# Inverter_540VDC_V2_2.net
KiCad netlist of a schematic drawn in Altium Designer
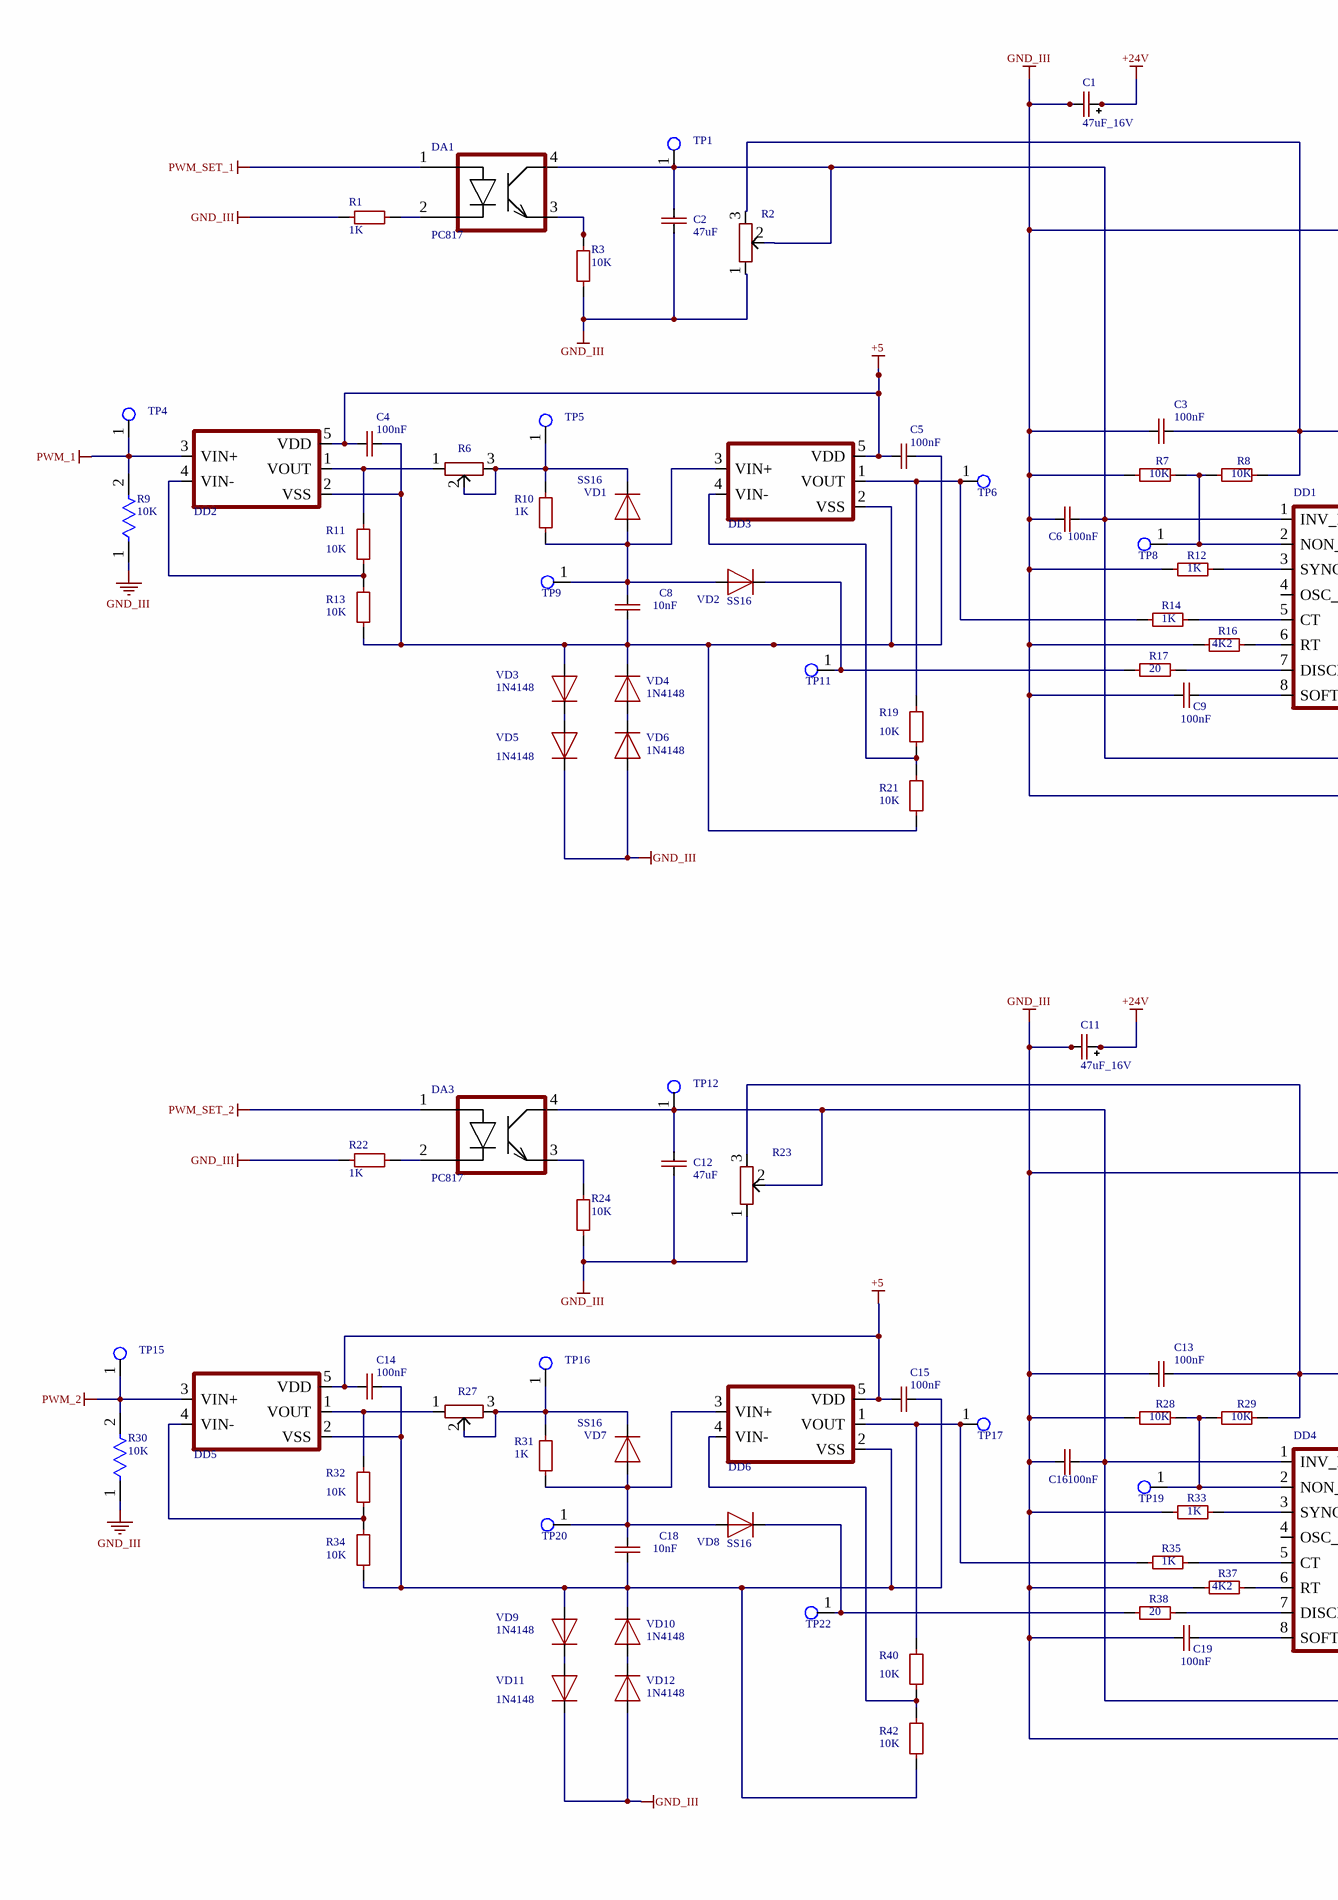
[diagram p0: Inverter_540VDC_V2.2.SchDoc, top left]
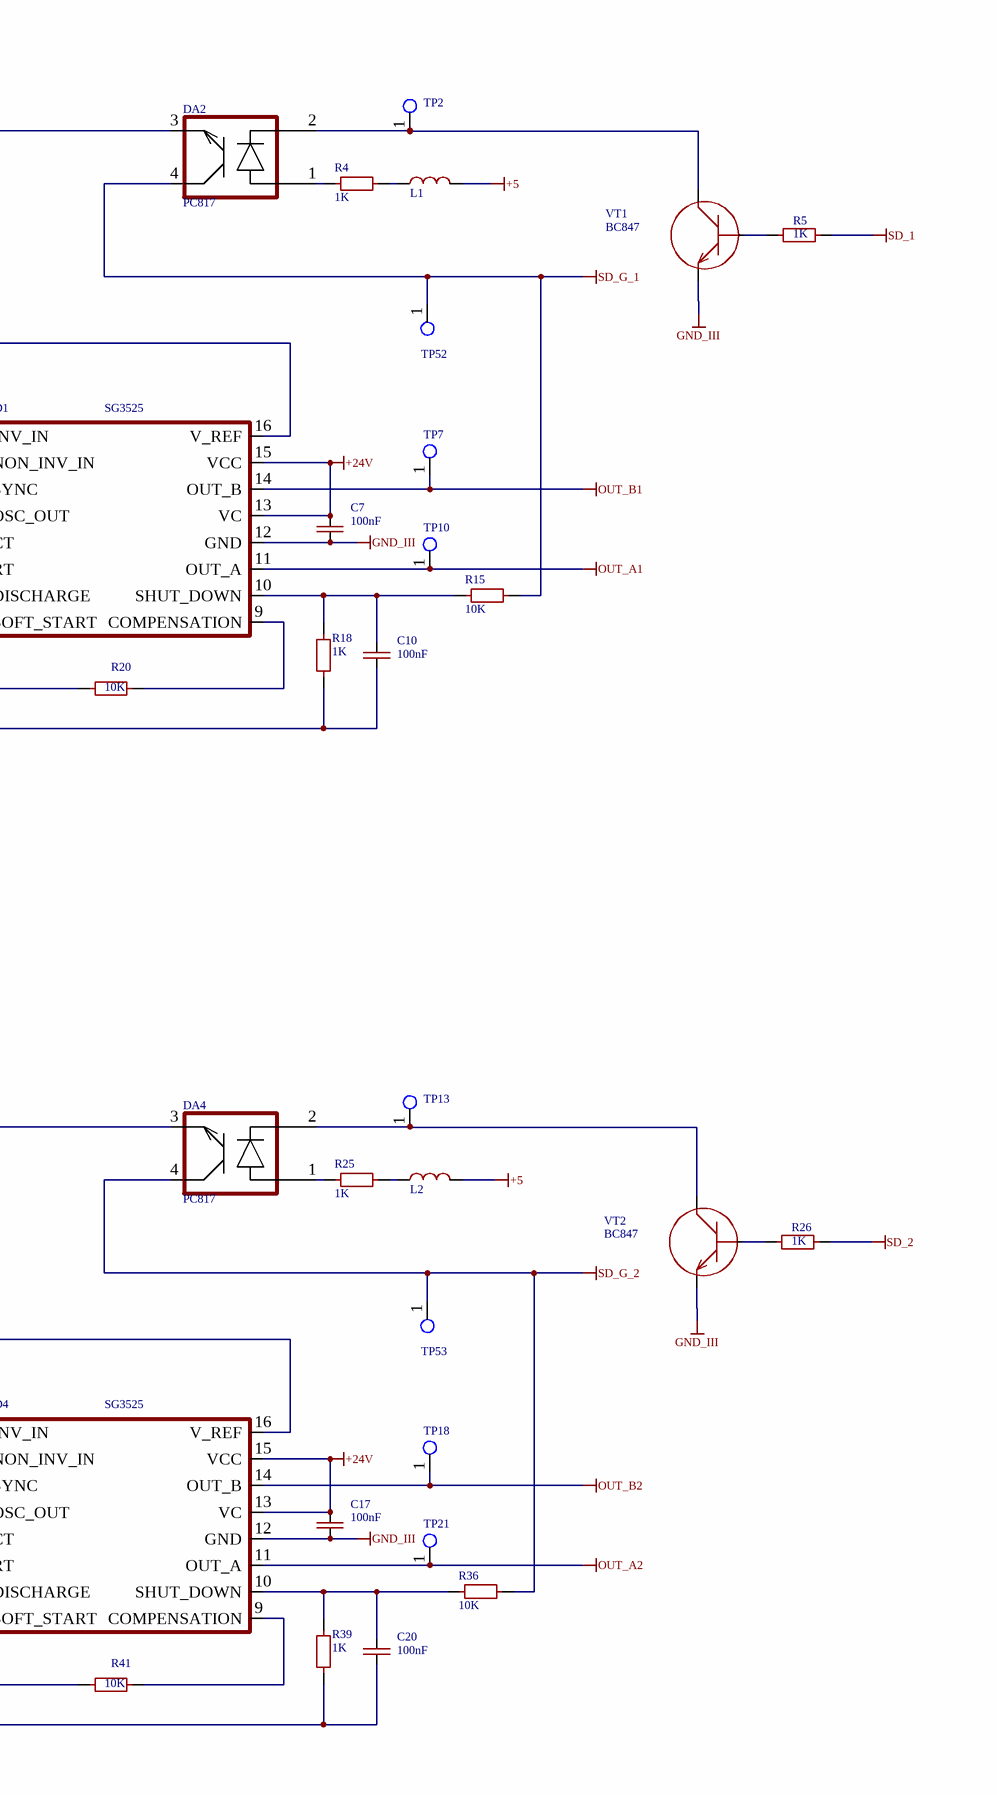
[diagram p1: Inverter_540VDC_V2.2.SchDoc, top right]
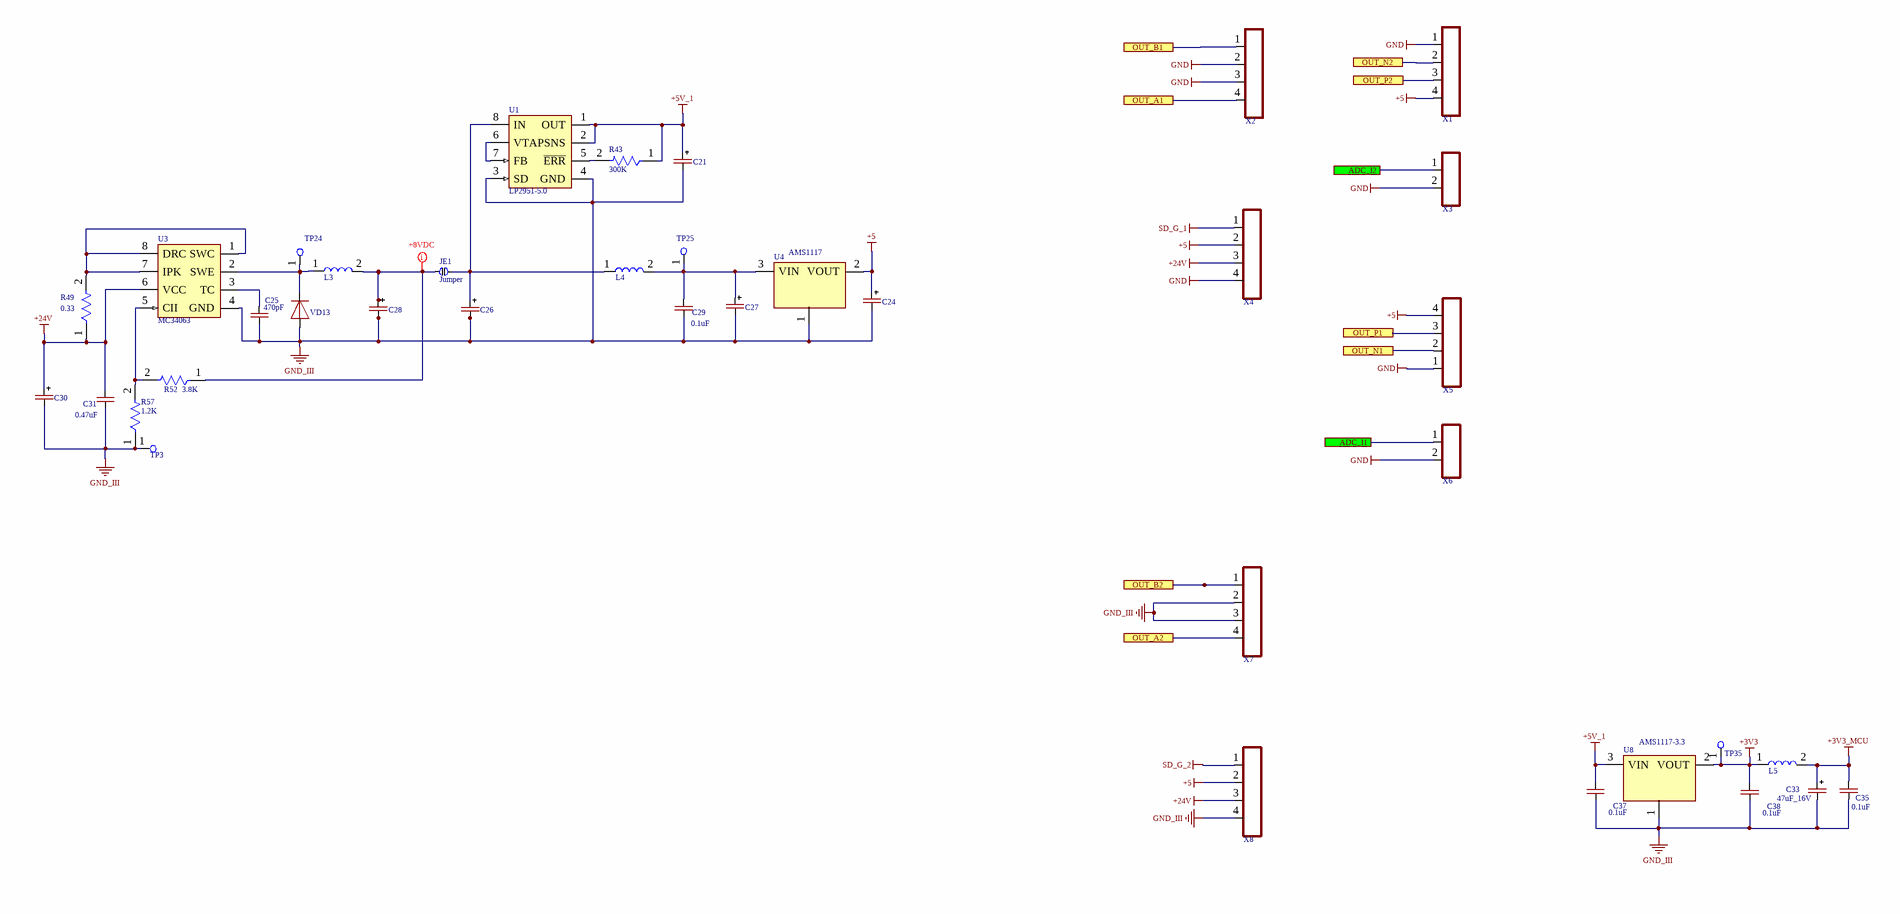
[diagram p2: Inverter_540VDC_V2.2.SchDoc, bottom left]
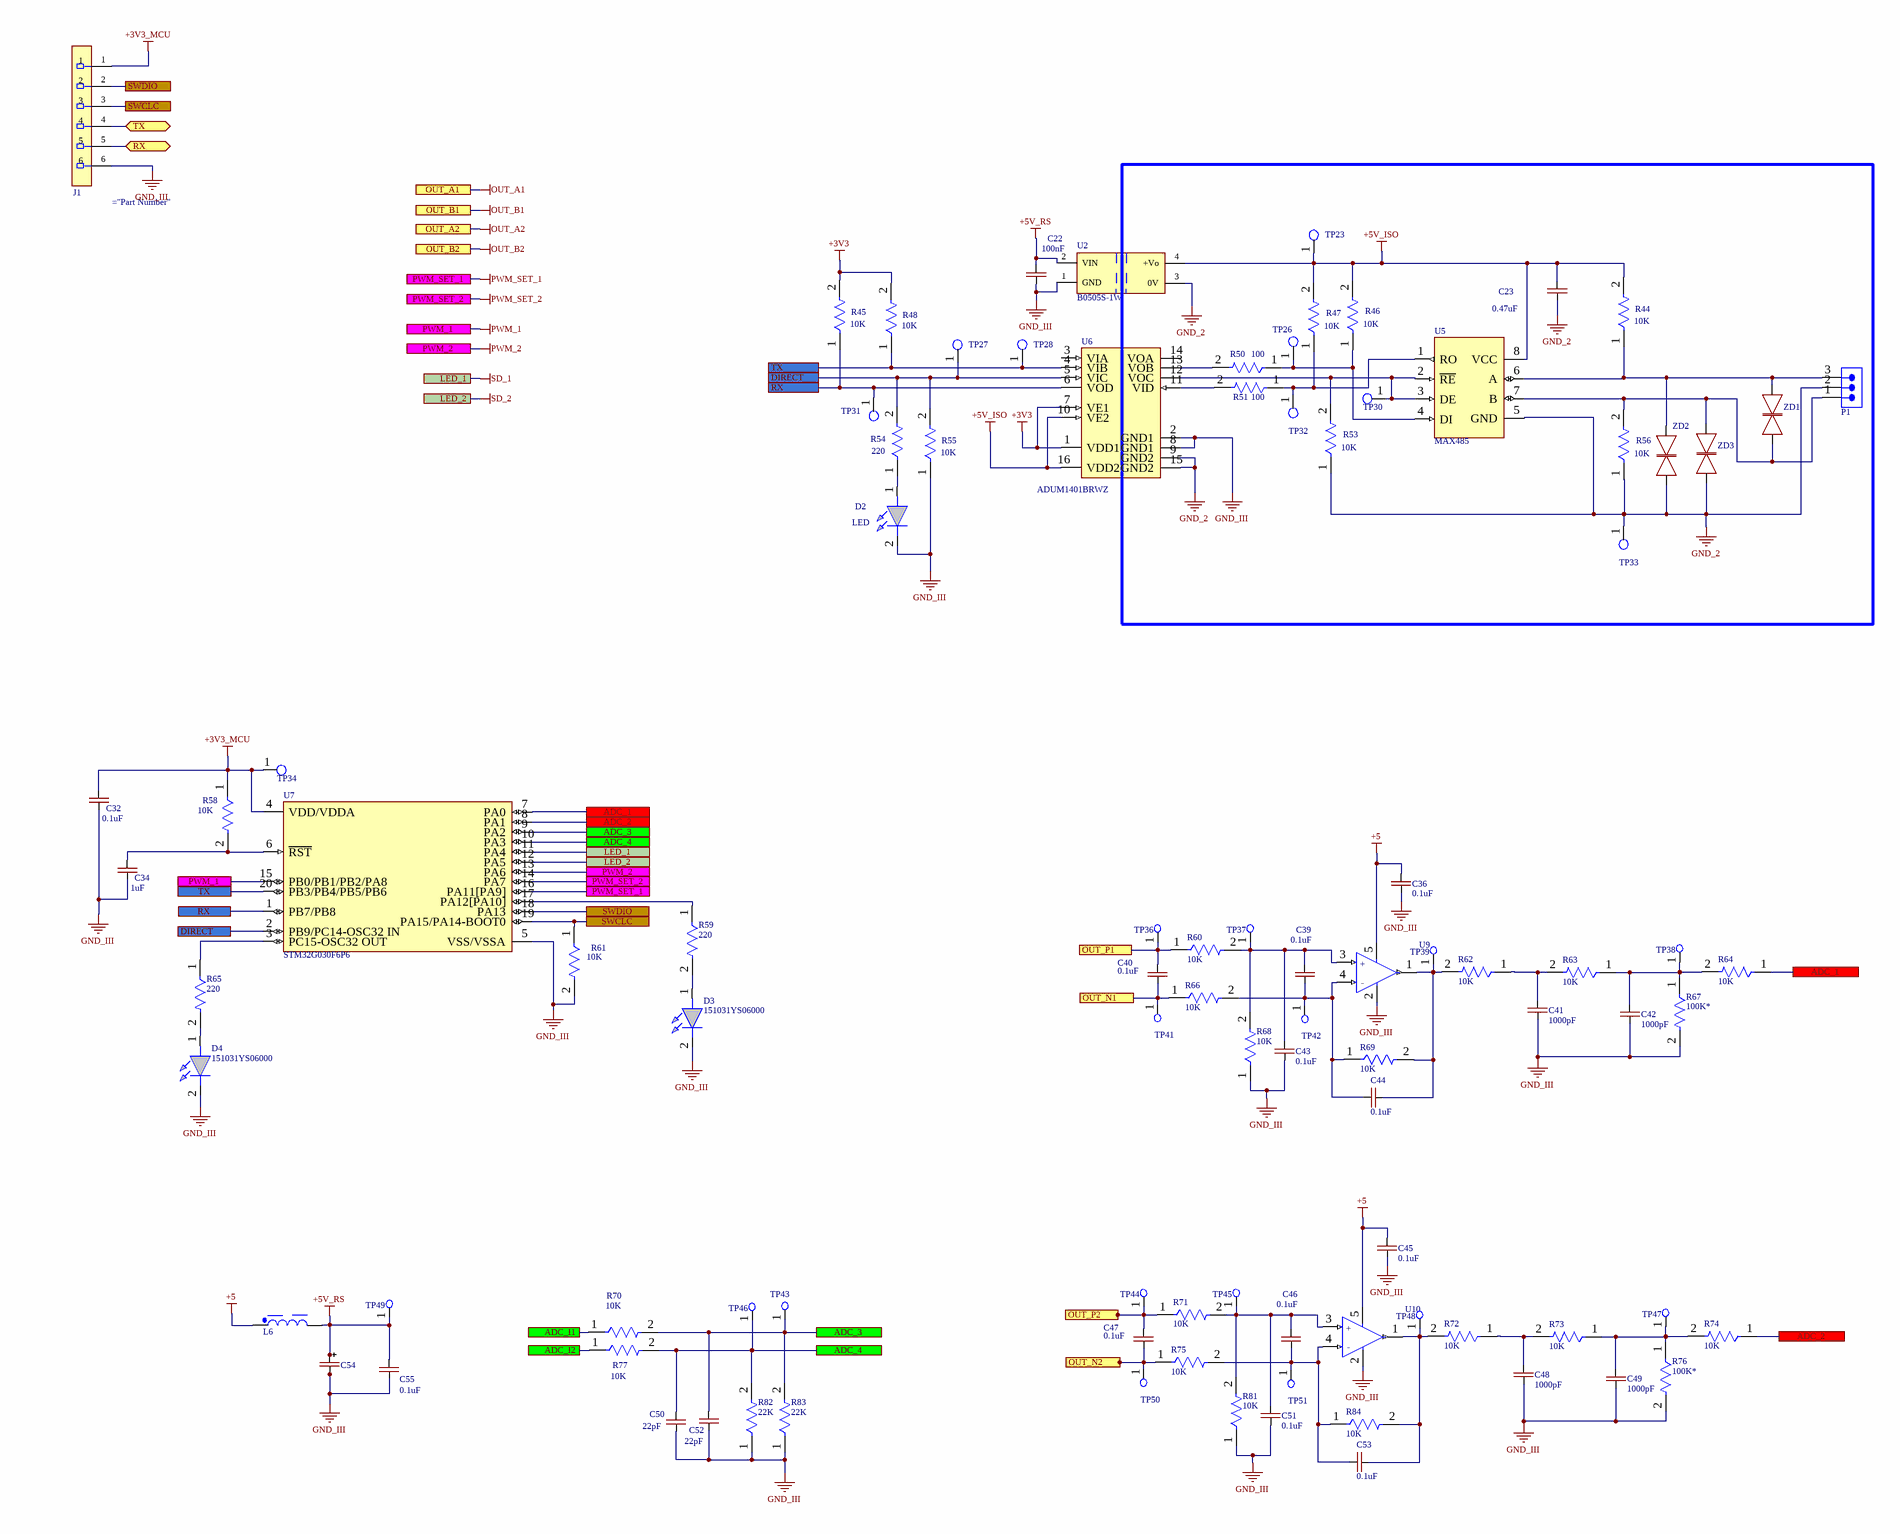
[diagram p3: Inverter_540VDC_V2.2.SchDoc, bottom right]

(export (version "E")
  (design (tool "Eeschema 10.0.6"))
  (components
    (comp (ref "C1")
      (value "47uF_16V")
      (footprint "CAP-TAN-D")
      (libsource (lib "PASSIVE_COMPONENTS") (part "CAP-POLAR"))
    )
    (comp (ref "C2")
      (value "47uF")
      (footprint "CAP-0805")
      (libsource (lib "PAS_COMPONENTS") (part "CAP-NON-POLAR"))
    )
    (comp (ref "C3")
      (value "100nF")
      (footprint "CAP-0805")
      (libsource (lib "PAS_COMPONENTS") (part "CAP-NON-POLAR"))
    )
    (comp (ref "C4")
      (value "100nF")
      (footprint "CAP-0805")
      (libsource (lib "PAS_COMPONENTS") (part "CAP-NON-POLAR"))
    )
    (comp (ref "C5")
      (value "100nF")
      (footprint "CAP-0805")
      (libsource (lib "PAS_COMPONENTS") (part "CAP-NON-POLAR"))
    )
    (comp (ref "C6")
      (value "100nF")
      (footprint "CAP-0805")
      (libsource (lib "PAS_COMPONENTS") (part "CAP-NON-POLAR"))
    )
    (comp (ref "C7")
      (value "100nF")
      (footprint "CAP-0805")
      (libsource (lib "PAS_COMPONENTS") (part "CAP-NON-POLAR"))
    )
    (comp (ref "C8")
      (value "10nF")
      (footprint "CAP-0805")
      (libsource (lib "PAS_COMPONENTS") (part "CAP-NON-POLAR"))
    )
    (comp (ref "C9")
      (value "100nF")
      (footprint "CAP-0805")
      (libsource (lib "PAS_COMPONENTS") (part "CAP-NON-POLAR"))
    )
    (comp (ref "C10")
      (value "100nF")
      (footprint "CAP-0805")
      (libsource (lib "PAS_COMPONENTS") (part "CAP-NON-POLAR"))
    )
    (comp (ref "C11")
      (value "47uF_16V")
      (footprint "CAP-TAN-D")
      (libsource (lib "PASSIVE_COMPONENTS") (part "CAP-POLAR"))
    )
    (comp (ref "C12")
      (value "47uF")
      (footprint "CAP-0805")
      (libsource (lib "PAS_COMPONENTS") (part "CAP-NON-POLAR"))
    )
    (comp (ref "C13")
      (value "100nF")
      (footprint "CAP-0805")
      (libsource (lib "PAS_COMPONENTS") (part "CAP-NON-POLAR"))
    )
    (comp (ref "C14")
      (value "100nF")
      (footprint "CAP-0805")
      (libsource (lib "PAS_COMPONENTS") (part "CAP-NON-POLAR"))
    )
    (comp (ref "C15")
      (value "100nF")
      (footprint "CAP-0805")
      (libsource (lib "PAS_COMPONENTS") (part "CAP-NON-POLAR"))
    )
    (comp (ref "C16")
      (value "100nF")
      (footprint "CAP-0805")
      (libsource (lib "PAS_COMPONENTS") (part "CAP-NON-POLAR"))
    )
    (comp (ref "C17")
      (value "100nF")
      (footprint "CAP-0805")
      (libsource (lib "PAS_COMPONENTS") (part "CAP-NON-POLAR"))
    )
    (comp (ref "C18")
      (value "10nF")
      (footprint "CAP-0805")
      (libsource (lib "PAS_COMPONENTS") (part "CAP-NON-POLAR"))
    )
    (comp (ref "C19")
      (value "100nF")
      (footprint "CAP-0805")
      (libsource (lib "PAS_COMPONENTS") (part "CAP-NON-POLAR"))
    )
    (comp (ref "C20")
      (value "100nF")
      (footprint "CAP-0805")
      (libsource (lib "PAS_COMPONENTS") (part "CAP-NON-POLAR"))
    )
    (comp (ref "C21")
      (value "CAP-POLAR")
      (footprint "CAP-TAN-C")
      (libsource (lib "PAS_COMPONENTS") (part "CAP-POLAR"))
    )
    (comp (ref "C22")
      (value "100nF")
      (footprint "CAP-0805")
      (libsource (lib "PASSIVE_COMPONENTS") (part "CAP-NON-POLAR"))
    )
    (comp (ref "C23")
      (value "0.47uF")
      (footprint "CAP-0805")
      (libsource (lib "PASSIVE_COMPONENTS") (part "CAP-NON-POLAR"))
    )
    (comp (ref "C24")
      (value "CAP-POLAR")
      (footprint "CAP-TAN-C")
      (libsource (lib "PAS_COMPONENTS") (part "CAP-POLAR"))
    )
    (comp (ref "C25")
      (value "470pF")
      (footprint "CAP-0805")
      (libsource (lib "PASSIVE_COMPONENTS") (part "CAP-NON-POLAR"))
    )
    (comp (ref "C26")
      (value "CAP-POLAR")
      (footprint "CAP-TAN-C")
      (libsource (lib "PAS_COMPONENTS") (part "CAP-POLAR"))
    )
    (comp (ref "C27")
      (value "CAP-POLAR")
      (footprint "CAP-TAN-C")
      (libsource (lib "PAS_COMPONENTS") (part "CAP-POLAR"))
    )
    (comp (ref "C28")
      (value "CAP-POLAR")
      (footprint "CAP-TAN-C")
      (libsource (lib "PAS_COMPONENTS") (part "CAP-POLAR"))
    )
    (comp (ref "C29")
      (value "0.1uF")
      (footprint "CAP-0805")
      (libsource (lib "PASSIVE_COMPONENTS") (part "CAP-NON-POLAR"))
    )
    (comp (ref "C30")
      (value "CAP-POLAR")
      (footprint "CAP-TAN-C")
      (libsource (lib "PAS_COMPONENTS") (part "CAP-POLAR"))
    )
    (comp (ref "C31")
      (value "0.47uF")
      (footprint "CAP-0805")
      (libsource (lib "PASSIVE_COMPONENTS") (part "CAP-NON-POLAR"))
    )
    (comp (ref "C32")
      (value "0.1uF")
      (footprint "CAP-0805")
      (libsource (lib "PASSIVE_COMPONENTS") (part "CAP-NON-POLAR"))
    )
    (comp (ref "C33")
      (value "47uF_16V")
      (footprint "CAP-TAN-D")
      (libsource (lib "PASSIVE_COMPONENTS") (part "CAP-POLAR"))
    )
    (comp (ref "C34")
      (value "1uF")
      (footprint "CAP-0805")
      (libsource (lib "PASSIVE_COMPONENTS") (part "CAP-NON-POLAR"))
    )
    (comp (ref "C35")
      (value "0.1uF")
      (footprint "CAP-0805")
      (libsource (lib "PASSIVE_COMPONENTS") (part "CAP-NON-POLAR"))
    )
    (comp (ref "C36")
      (value "0.1uF")
      (footprint "CAP-0805")
      (libsource (lib "PASSIVE_COMPONENTS") (part "CAP-NON-POLAR"))
    )
    (comp (ref "C37")
      (value "0.1uF")
      (footprint "CAP-0805")
      (libsource (lib "PASSIVE_COMPONENTS") (part "CAP-NON-POLAR"))
    )
    (comp (ref "C38")
      (value "0.1uF")
      (footprint "CAP-0805")
      (libsource (lib "PASSIVE_COMPONENTS") (part "CAP-NON-POLAR"))
    )
    (comp (ref "C39")
      (value "0.1uF")
      (footprint "CAP-0805")
      (libsource (lib "PASSIVE_COMPONENTS") (part "CAP-NON-POLAR"))
    )
    (comp (ref "C40")
      (value "0.1uF")
      (footprint "CAP-0805")
      (libsource (lib "PASSIVE_COMPONENTS") (part "CAP-NON-POLAR"))
    )
    (comp (ref "C41")
      (value "1000pF")
      (footprint "CAP-0805")
      (libsource (lib "PASSIVE_COMPONENTS") (part "CAP-NON-POLAR"))
    )
    (comp (ref "C42")
      (value "1000pF")
      (footprint "CAP-0805")
      (libsource (lib "PASSIVE_COMPONENTS") (part "CAP-NON-POLAR"))
    )
    (comp (ref "C43")
      (value "0.1uF")
      (footprint "CAP-0805")
      (libsource (lib "PASSIVE_COMPONENTS") (part "CAP-NON-POLAR"))
    )
    (comp (ref "C44")
      (value "0.1uF")
      (footprint "CAP-0805")
      (libsource (lib "PASSIVE_COMPONENTS") (part "CAP-NON-POLAR"))
    )
    (comp (ref "C45")
      (value "0.1uF")
      (footprint "CAP-0805")
      (libsource (lib "PASSIVE_COMPONENTS") (part "CAP-NON-POLAR"))
    )
    (comp (ref "C46")
      (value "0.1uF")
      (footprint "CAP-0805")
      (libsource (lib "PASSIVE_COMPONENTS") (part "CAP-NON-POLAR"))
    )
    (comp (ref "C47")
      (value "0.1uF")
      (footprint "CAP-0805")
      (libsource (lib "PASSIVE_COMPONENTS") (part "CAP-NON-POLAR"))
    )
    (comp (ref "C48")
      (value "1000pF")
      (footprint "CAP-0805")
      (libsource (lib "PASSIVE_COMPONENTS") (part "CAP-NON-POLAR"))
    )
    (comp (ref "C49")
      (value "1000pF")
      (footprint "CAP-0805")
      (libsource (lib "PASSIVE_COMPONENTS") (part "CAP-NON-POLAR"))
    )
    (comp (ref "C50")
      (value "22pF")
      (footprint "CAP-0805")
      (libsource (lib "PASSIVE_COMPONENTS") (part "CAP-NON-POLAR"))
    )
    (comp (ref "C51")
      (value "0.1uF")
      (footprint "CAP-0805")
      (libsource (lib "PASSIVE_COMPONENTS") (part "CAP-NON-POLAR"))
    )
    (comp (ref "C52")
      (value "22pF")
      (footprint "CAP-0805")
      (libsource (lib "PASSIVE_COMPONENTS") (part "CAP-NON-POLAR"))
    )
    (comp (ref "C53")
      (value "0.1uF")
      (footprint "CAP-0805")
      (libsource (lib "PASSIVE_COMPONENTS") (part "CAP-NON-POLAR"))
    )
    (comp (ref "C54")
      (value "CAP-POLAR")
      (footprint "CAP-TAN-C")
      (libsource (lib "PAS_COMPONENTS") (part "CAP-POLAR"))
    )
    (comp (ref "C55")
      (value "0.1uF")
      (footprint "CAP-0805")
      (libsource (lib "PASSIVE_COMPONENTS") (part "CAP-NON-POLAR"))
    )
    (comp (ref "D2")
      (value "LED")
      (footprint "LED_RED")
      (description "WURTH ELEKTRONIK - 151031YS06000 - LED, Yellow, Through Hole, T-1 (3mm), 30 mA, 2 V, 590 nm")
      (fields
        (field (name "MANUFACTURER_PART_NUMBER") "151031YS06000")
        (field (name "MOUSER PART NUMBER") "710-151031YS06000")
      )
      (libsource (lib "Optic-LED") (part "LED"))
    )
    (comp (ref "D3")
      (value "151031YS06000")
      (footprint "LED_RED")
      (description "WURTH ELEKTRONIK - 151031YS06000 - LED, Yellow, Through Hole, T-1 (3mm), 30 mA, 2 V, 590 nm")
      (fields (field (name "MOUSER PART NUMBER") "710-151031YS06000"))
      (libsource (lib "Optic-LED") (part "LED"))
    )
    (comp (ref "D4")
      (value "151031YS06000")
      (footprint "LED_RED")
      (description "WURTH ELEKTRONIK - 151031YS06000 - LED, Yellow, Through Hole, T-1 (3mm), 30 mA, 2 V, 590 nm")
      (fields (field (name "MOUSER PART NUMBER") "710-151031YS06000"))
      (libsource (lib "Optic-LED") (part "LED"))
    )
    (comp (ref "DA1") (value "PC817") (footprint "4-SMD") (libsource (lib "PC817") (part "PC817")))
    (comp (ref "DA2") (value "PC817") (footprint "4-SMD") (libsource (lib "") (part "PC817_1")))
    (comp (ref "DA3") (value "PC817") (footprint "4-SMD") (libsource (lib "PC817") (part "PC817")))
    (comp (ref "DA4") (value "PC817") (footprint "4-SMD") (libsource (lib "") (part "PC817_1")))
    (comp (ref "DD1") (value "SG3525") (footprint "SO16-150") (libsource (lib "SG3525") (part "SG3525")))
    (comp (ref "DD2") (value "MCP6001") (footprint "SOT23-5") (libsource (lib "MCP6001") (part "MCP6001")))
    (comp (ref "DD3") (value "MCP6001") (footprint "SOT23-5") (libsource (lib "MCP6001") (part "MCP6001")))
    (comp (ref "DD4") (value "SG3525") (footprint "SO16-150") (libsource (lib "SG3525") (part "SG3525")))
    (comp (ref "DD5") (value "MCP6001") (footprint "SOT23-5") (libsource (lib "MCP6001") (part "MCP6001")))
    (comp (ref "DD6") (value "MCP6001") (footprint "SOT23-5") (libsource (lib "MCP6001") (part "MCP6001")))
    (comp (ref "J1")
      (value "SWR25X-NRTC-S06-ST-BA")
      (footprint "Sullins_SWR25X-NRTC-S06-ST-BA_MFG")
      (libsource (lib "Conn_Sullins_SWR25X-NRTC-S06-ST-BA_eec") (part "SWR25X-NRTC-S06-ST-BA"))
    )
    (comp (ref "JE1") (value "Jumper") (footprint "JE") (libsource (lib "Connectors") (part "JE")))
    (comp (ref "L1")
      (value "IND-CONST")
      (footprint "IND-5852")
      (libsource (lib "PAS_COMPONENTS") (part "IND-CONST"))
    )
    (comp (ref "L2")
      (value "IND-CONST")
      (footprint "IND-5852")
      (libsource (lib "PAS_COMPONENTS") (part "IND-CONST"))
    )
    (comp (ref "L3")
      (value "Coil")
      (footprint "Coil_4.5x4.5_mm")
      (libsource (lib "Transformers") (part "Coil"))
    )
    (comp (ref "L4")
      (value "Coil")
      (footprint "Coil_4.5x4.5_mm")
      (libsource (lib "Transformers") (part "Coil"))
    )
    (comp (ref "L5")
      (value "Coil")
      (footprint "Coil_4.5x4.5_mm")
      (libsource (lib "Transformers") (part "Coil"))
    )
    (comp (ref "L6")
      (value "1000µH, 0.3A")
      (footprint "WE-PD2_7850")
      (description "WE-PD2 SMT Power Inductor, size 7850, 1000µH, 0.3A, 3.3Ω")
      (fields
        (field (name "MANUFACTURER PART NUMBER") "74477530")
        (field (name "MANUFACTURER") "Wurth Elektronik")
      )
      (libsource (lib "WE-PD2 (rev22d)") (part "74477530"))
    )
    (comp (ref "P1")
      (value "691701530003B")
      (footprint "691701530003B")
      (description "WR-TBL Series 7015B Open Horizontal PCB Header, SMT, pitch 5.08mm, 3p")
      (fields (field (name "MANUFACTURER") "Wurth Elektronik"))
      (libsource (lib "Altium_WR-TBL (rev23d)") (part "691701530003B"))
    )
    (comp (ref "R1")
      (value "1K")
      (footprint "RES-0805")
      (description "10K")
      (libsource (lib "PAS_COMPONENTS") (part "RES-CONST"))
    )
    (comp (ref "R2") (value "3296") (footprint "3296W") (libsource (lib "3296") (part "3296")))
    (comp (ref "R3")
      (value "10K")
      (footprint "RES-0805")
      (libsource (lib "PAS_COMPONENTS") (part "RES-CONST"))
    )
    (comp (ref "R4")
      (value "1K")
      (footprint "RES-0805")
      (libsource (lib "PAS_COMPONENTS") (part "RES-CONST"))
    )
    (comp (ref "R5")
      (value "1K")
      (footprint "RES-0805")
      (libsource (lib "PAS_COMPONENTS") (part "RES-CONST"))
    )
    (comp (ref "R6") (value "3296") (footprint "3296W") (libsource (lib "") (part "3296_1")))
    (comp (ref "R7")
      (value "10K")
      (footprint "RES-0805")
      (libsource (lib "PAS_COMPONENTS") (part "RES-CONST"))
    )
    (comp (ref "R8")
      (value "10K")
      (footprint "RES-0805")
      (libsource (lib "PAS_COMPONENTS") (part "RES-CONST"))
    )
    (comp (ref "R9")
      (value "10K")
      (footprint "RES-0805")
      (libsource (lib "PASSIVE_COMPONENTS") (part "RES-CONST"))
    )
    (comp (ref "R10")
      (value "1K")
      (footprint "RES-0805")
      (libsource (lib "PAS_COMPONENTS") (part "RES-CONST"))
    )
    (comp (ref "R11")
      (value "10K")
      (footprint "RES-0805")
      (libsource (lib "PAS_COMPONENTS") (part "RES-CONST"))
    )
    (comp (ref "R12")
      (value "1K")
      (footprint "RES-0805")
      (libsource (lib "PAS_COMPONENTS") (part "RES-CONST"))
    )
    (comp (ref "R13")
      (value "10K")
      (footprint "RES-0805")
      (libsource (lib "PAS_COMPONENTS") (part "RES-CONST"))
    )
    (comp (ref "R14")
      (value "1K")
      (footprint "RES-0805")
      (libsource (lib "PAS_COMPONENTS") (part "RES-CONST"))
    )
    (comp (ref "R15")
      (value "10K")
      (footprint "RES-0805")
      (libsource (lib "PAS_COMPONENTS") (part "RES-CONST"))
    )
    (comp (ref "R16")
      (value "4K2")
      (footprint "RES-0805")
      (libsource (lib "PAS_COMPONENTS") (part "RES-CONST"))
    )
    (comp (ref "R17")
      (value "20")
      (footprint "RES-0805")
      (description "1K")
      (libsource (lib "PAS_COMPONENTS") (part "RES-CONST"))
    )
    (comp (ref "R18")
      (value "1K")
      (footprint "RES-0805")
      (libsource (lib "PAS_COMPONENTS") (part "RES-CONST"))
    )
    (comp (ref "R19")
      (value "10K")
      (footprint "RES-0805")
      (libsource (lib "PAS_COMPONENTS") (part "RES-CONST"))
    )
    (comp (ref "R20")
      (value "10K")
      (footprint "RES-0805")
      (libsource (lib "PAS_COMPONENTS") (part "RES-CONST"))
    )
    (comp (ref "R21")
      (value "10K")
      (footprint "RES-0805")
      (libsource (lib "PAS_COMPONENTS") (part "RES-CONST"))
    )
    (comp (ref "R22")
      (value "1K")
      (footprint "RES-0805")
      (description "10K")
      (libsource (lib "PAS_COMPONENTS") (part "RES-CONST"))
    )
    (comp (ref "R23") (value "3296W") (footprint "3296W") (libsource (lib "3296W") (part "3296W")))
    (comp (ref "R24")
      (value "10K")
      (footprint "RES-0805")
      (libsource (lib "PAS_COMPONENTS") (part "RES-CONST"))
    )
    (comp (ref "R25")
      (value "1K")
      (footprint "RES-0805")
      (libsource (lib "PAS_COMPONENTS") (part "RES-CONST"))
    )
    (comp (ref "R26")
      (value "1K")
      (footprint "RES-0805")
      (libsource (lib "PAS_COMPONENTS") (part "RES-CONST"))
    )
    (comp (ref "R27") (value "3296") (footprint "3296W") (libsource (lib "") (part "3296_1")))
    (comp (ref "R28")
      (value "10K")
      (footprint "RES-0805")
      (libsource (lib "PAS_COMPONENTS") (part "RES-CONST"))
    )
    (comp (ref "R29")
      (value "10K")
      (footprint "RES-0805")
      (libsource (lib "PAS_COMPONENTS") (part "RES-CONST"))
    )
    (comp (ref "R30")
      (value "10K")
      (footprint "RES-0805")
      (libsource (lib "PASSIVE_COMPONENTS") (part "RES-CONST"))
    )
    (comp (ref "R31")
      (value "1K")
      (footprint "RES-0805")
      (libsource (lib "PAS_COMPONENTS") (part "RES-CONST"))
    )
    (comp (ref "R32")
      (value "10K")
      (footprint "RES-0805")
      (libsource (lib "PAS_COMPONENTS") (part "RES-CONST"))
    )
    (comp (ref "R33")
      (value "1K")
      (footprint "RES-0805")
      (libsource (lib "PAS_COMPONENTS") (part "RES-CONST"))
    )
    (comp (ref "R34")
      (value "10K")
      (footprint "RES-0805")
      (libsource (lib "PAS_COMPONENTS") (part "RES-CONST"))
    )
    (comp (ref "R35")
      (value "1K")
      (footprint "RES-0805")
      (libsource (lib "PAS_COMPONENTS") (part "RES-CONST"))
    )
    (comp (ref "R36")
      (value "10K")
      (footprint "RES-0805")
      (libsource (lib "PAS_COMPONENTS") (part "RES-CONST"))
    )
    (comp (ref "R37")
      (value "4K2")
      (footprint "RES-0805")
      (libsource (lib "PAS_COMPONENTS") (part "RES-CONST"))
    )
    (comp (ref "R38")
      (value "20")
      (footprint "RES-0805")
      (description "1K")
      (libsource (lib "PAS_COMPONENTS") (part "RES-CONST"))
    )
    (comp (ref "R39")
      (value "1K")
      (footprint "RES-0805")
      (libsource (lib "PAS_COMPONENTS") (part "RES-CONST"))
    )
    (comp (ref "R40")
      (value "10K")
      (footprint "RES-0805")
      (libsource (lib "PAS_COMPONENTS") (part "RES-CONST"))
    )
    (comp (ref "R41")
      (value "10K")
      (footprint "RES-0805")
      (libsource (lib "PAS_COMPONENTS") (part "RES-CONST"))
    )
    (comp (ref "R42")
      (value "10K")
      (footprint "RES-0805")
      (libsource (lib "PAS_COMPONENTS") (part "RES-CONST"))
    )
    (comp (ref "R43")
      (value "300K")
      (footprint "RES-0805")
      (libsource (lib "PASSIVE_COMPONENTS") (part "RES-CONST"))
    )
    (comp (ref "R44")
      (value "10K")
      (footprint "RES-0805")
      (libsource (lib "PASSIVE_COMPONENTS") (part "RES-CONST"))
    )
    (comp (ref "R45")
      (value "10K")
      (footprint "RES-0805")
      (libsource (lib "PASSIVE_COMPONENTS") (part "RES-CONST"))
    )
    (comp (ref "R46")
      (value "10K")
      (footprint "RES-0805")
      (libsource (lib "PASSIVE_COMPONENTS") (part "RES-CONST"))
    )
    (comp (ref "R47")
      (value "10K")
      (footprint "RES-0805")
      (libsource (lib "PASSIVE_COMPONENTS") (part "RES-CONST"))
    )
    (comp (ref "R48")
      (value "10K")
      (footprint "RES-0805")
      (libsource (lib "PASSIVE_COMPONENTS") (part "RES-CONST"))
    )
    (comp (ref "R49")
      (value "0.33")
      (footprint "RES-1206")
      (libsource (lib "PASSIVE_COMPONENTS") (part "RES-CONST"))
    )
    (comp (ref "R50")
      (value "100")
      (footprint "RES-0805")
      (libsource (lib "PASSIVE_COMPONENTS") (part "RES-CONST"))
    )
    (comp (ref "R51")
      (value "100")
      (footprint "RES-0805")
      (libsource (lib "PASSIVE_COMPONENTS") (part "RES-CONST"))
    )
    (comp (ref "R52")
      (value "3.8K")
      (footprint "RES-0805")
      (description "10K")
      (libsource (lib "PASSIVE_COMPONENTS") (part "RES-CONST"))
    )
    (comp (ref "R53")
      (value "10K")
      (footprint "RES-0805")
      (libsource (lib "PASSIVE_COMPONENTS") (part "RES-CONST"))
    )
    (comp (ref "R54")
      (value "220")
      (footprint "RES-0805")
      (libsource (lib "PASSIVE_COMPONENTS") (part "RES-CONST"))
    )
    (comp (ref "R55")
      (value "10K")
      (footprint "RES-0805")
      (libsource (lib "PASSIVE_COMPONENTS") (part "RES-CONST"))
    )
    (comp (ref "R56")
      (value "10K")
      (footprint "RES-0805")
      (libsource (lib "PASSIVE_COMPONENTS") (part "RES-CONST"))
    )
    (comp (ref "R57")
      (value "1.2K")
      (footprint "RES-0805")
      (libsource (lib "PASSIVE_COMPONENTS") (part "RES-CONST"))
    )
    (comp (ref "R58")
      (value "10K")
      (footprint "RES-0805")
      (libsource (lib "PASSIVE_COMPONENTS") (part "RES-CONST"))
    )
    (comp (ref "R59")
      (value "220")
      (footprint "RES-0805")
      (libsource (lib "PASSIVE_COMPONENTS") (part "RES-CONST"))
    )
    (comp (ref "R60")
      (value "10K")
      (footprint "RES-0805")
      (libsource (lib "PASSIVE_COMPONENTS") (part "RES-CONST"))
    )
    (comp (ref "R61")
      (value "10K")
      (footprint "RES-0805")
      (libsource (lib "PASSIVE_COMPONENTS") (part "RES-CONST"))
    )
    (comp (ref "R62")
      (value "10K")
      (footprint "RES-0805")
      (libsource (lib "PASSIVE_COMPONENTS") (part "RES-CONST"))
    )
    (comp (ref "R63")
      (value "10K")
      (footprint "RES-0805")
      (libsource (lib "PASSIVE_COMPONENTS") (part "RES-CONST"))
    )
    (comp (ref "R64")
      (value "10K")
      (footprint "RES-0805")
      (libsource (lib "PASSIVE_COMPONENTS") (part "RES-CONST"))
    )
    (comp (ref "R65")
      (value "220")
      (footprint "RES-0805")
      (libsource (lib "PASSIVE_COMPONENTS") (part "RES-CONST"))
    )
    (comp (ref "R66")
      (value "10K")
      (footprint "RES-0805")
      (libsource (lib "PASSIVE_COMPONENTS") (part "RES-CONST"))
    )
    (comp (ref "R67")
      (value "100K*")
      (footprint "RES-0805")
      (libsource (lib "PASSIVE_COMPONENTS") (part "RES-CONST"))
    )
    (comp (ref "R68")
      (value "10K")
      (footprint "RES-0805")
      (libsource (lib "PASSIVE_COMPONENTS") (part "RES-CONST"))
    )
    (comp (ref "R69")
      (value "10K")
      (footprint "RES-0805")
      (libsource (lib "PASSIVE_COMPONENTS") (part "RES-CONST"))
    )
    (comp (ref "R70")
      (value "10K")
      (footprint "RES-0805")
      (libsource (lib "PASSIVE_COMPONENTS") (part "RES-CONST"))
    )
    (comp (ref "R71")
      (value "10K")
      (footprint "RES-0805")
      (libsource (lib "PASSIVE_COMPONENTS") (part "RES-CONST"))
    )
    (comp (ref "R72")
      (value "10K")
      (footprint "RES-0805")
      (libsource (lib "PASSIVE_COMPONENTS") (part "RES-CONST"))
    )
    (comp (ref "R73")
      (value "10K")
      (footprint "RES-0805")
      (libsource (lib "PASSIVE_COMPONENTS") (part "RES-CONST"))
    )
    (comp (ref "R74")
      (value "10K")
      (footprint "RES-0805")
      (libsource (lib "PASSIVE_COMPONENTS") (part "RES-CONST"))
    )
    (comp (ref "R75")
      (value "10K")
      (footprint "RES-0805")
      (libsource (lib "PASSIVE_COMPONENTS") (part "RES-CONST"))
    )
    (comp (ref "R76")
      (value "100K*")
      (footprint "RES-0805")
      (libsource (lib "PASSIVE_COMPONENTS") (part "RES-CONST"))
    )
    (comp (ref "R77")
      (value "10K")
      (footprint "RES-0805")
      (libsource (lib "PASSIVE_COMPONENTS") (part "RES-CONST"))
    )
    (comp (ref "R81")
      (value "10K")
      (footprint "RES-0805")
      (libsource (lib "PASSIVE_COMPONENTS") (part "RES-CONST"))
    )
    (comp (ref "R82")
      (value "22K")
      (footprint "RES-0805")
      (libsource (lib "PASSIVE_COMPONENTS") (part "RES-CONST"))
    )
    (comp (ref "R83")
      (value "22K")
      (footprint "RES-0805")
      (libsource (lib "PASSIVE_COMPONENTS") (part "RES-CONST"))
    )
    (comp (ref "R84")
      (value "10K")
      (footprint "RES-0805")
      (libsource (lib "PASSIVE_COMPONENTS") (part "RES-CONST"))
    )
    (comp (ref "TP1")
      (value "Test_Point_PCB")
      (footprint "Test_Point")
      (description "Test_Point")
      (libsource (lib "TEST_POINT") (part "TP_PCB?"))
    )
    (comp (ref "TP2")
      (value "Test_Point_PCB")
      (footprint "Test_Point")
      (description "Test_Point")
      (libsource (lib "TEST_POINT") (part "TP_PCB?"))
    )
    (comp (ref "TP3")
      (value "Test_Point_PCB")
      (footprint "Test_Point")
      (description "Test_Point")
      (libsource (lib "Connectors") (part "TP_PCB?"))
    )
    (comp (ref "TP4")
      (value "Test_Point_PCB")
      (footprint "Test_Point")
      (description "Test_Point")
      (libsource (lib "TEST_POINT") (part "TP_PCB?"))
    )
    (comp (ref "TP5")
      (value "Test_Point_PCB")
      (footprint "Test_Point")
      (description "Test_Point")
      (libsource (lib "TEST_POINT") (part "TP_PCB?"))
    )
    (comp (ref "TP6")
      (value "Test_Point_PCB")
      (footprint "Test_Point")
      (description "Test_Point")
      (libsource (lib "TEST_POINT") (part "TP_PCB?"))
    )
    (comp (ref "TP7")
      (value "Test_Point_PCB")
      (footprint "Test_Point")
      (description "Test_Point")
      (libsource (lib "TEST_POINT") (part "TP_PCB?"))
    )
    (comp (ref "TP8")
      (value "Test_Point_PCB")
      (footprint "Test_Point")
      (description "Test_Point")
      (libsource (lib "TEST_POINT") (part "TP_PCB?"))
    )
    (comp (ref "TP9")
      (value "Test_Point_PCB")
      (footprint "Test_Point")
      (description "Test_Point")
      (libsource (lib "TEST_POINT") (part "TP_PCB?"))
    )
    (comp (ref "TP10")
      (value "Test_Point_PCB")
      (footprint "Test_Point")
      (description "Test_Point")
      (libsource (lib "TEST_POINT") (part "TP_PCB?"))
    )
    (comp (ref "TP11")
      (value "Test_Point_PCB")
      (footprint "Test_Point")
      (description "Test_Point")
      (libsource (lib "TEST_POINT") (part "TP_PCB?"))
    )
    (comp (ref "TP12")
      (value "Test_Point_PCB")
      (footprint "Test_Point")
      (description "Test_Point")
      (libsource (lib "TEST_POINT") (part "TP_PCB?"))
    )
    (comp (ref "TP13")
      (value "Test_Point_PCB")
      (footprint "Test_Point")
      (description "Test_Point")
      (libsource (lib "TEST_POINT") (part "TP_PCB?"))
    )
    (comp (ref "TP15")
      (value "Test_Point_PCB")
      (footprint "Test_Point")
      (description "Test_Point")
      (libsource (lib "TEST_POINT") (part "TP_PCB?"))
    )
    (comp (ref "TP16")
      (value "Test_Point_PCB")
      (footprint "Test_Point")
      (description "Test_Point")
      (libsource (lib "TEST_POINT") (part "TP_PCB?"))
    )
    (comp (ref "TP17")
      (value "Test_Point_PCB")
      (footprint "Test_Point")
      (description "Test_Point")
      (libsource (lib "TEST_POINT") (part "TP_PCB?"))
    )
    (comp (ref "TP18")
      (value "Test_Point_PCB")
      (footprint "Test_Point")
      (description "Test_Point")
      (libsource (lib "TEST_POINT") (part "TP_PCB?"))
    )
    (comp (ref "TP19")
      (value "Test_Point_PCB")
      (footprint "Test_Point")
      (description "Test_Point")
      (libsource (lib "TEST_POINT") (part "TP_PCB?"))
    )
    (comp (ref "TP20")
      (value "Test_Point_PCB")
      (footprint "Test_Point")
      (description "Test_Point")
      (libsource (lib "TEST_POINT") (part "TP_PCB?"))
    )
    (comp (ref "TP21")
      (value "Test_Point_PCB")
      (footprint "Test_Point")
      (description "Test_Point")
      (libsource (lib "TEST_POINT") (part "TP_PCB?"))
    )
    (comp (ref "TP22")
      (value "Test_Point_PCB")
      (footprint "Test_Point")
      (description "Test_Point")
      (libsource (lib "TEST_POINT") (part "TP_PCB?"))
    )
    (comp (ref "TP23")
      (value "Test_Point_PCB")
      (footprint "Test_Point")
      (description "Test_Point")
      (libsource (lib "Test_Point") (part "TP_PCB?"))
    )
    (comp (ref "TP24")
      (value "Test_Point_PCB")
      (footprint "Test_Point")
      (description "Test_Point")
      (libsource (lib "Connectors") (part "TP_PCB?"))
    )
    (comp (ref "TP25")
      (value "Test_Point_PCB")
      (footprint "Test_Point")
      (description "Test_Point")
      (libsource (lib "Connectors") (part "TP_PCB?"))
    )
    (comp (ref "TP26")
      (value "Test_Point_PCB")
      (footprint "Test_Point")
      (description "Test_Point")
      (libsource (lib "Test_Point") (part "TP_PCB?"))
    )
    (comp (ref "TP27")
      (value "Test_Point_PCB")
      (footprint "Test_Point")
      (description "Test_Point")
      (libsource (lib "Test_Point") (part "TP_PCB?"))
    )
    (comp (ref "TP28")
      (value "Test_Point_PCB")
      (footprint "Test_Point")
      (description "Test_Point")
      (libsource (lib "Test_Point") (part "TP_PCB?"))
    )
    (comp (ref "TP30")
      (value "Test_Point_PCB")
      (footprint "Test_Point")
      (description "Test_Point")
      (libsource (lib "Test_Point") (part "TP_PCB?"))
    )
    (comp (ref "TP31")
      (value "Test_Point_PCB")
      (footprint "Test_Point")
      (description "Test_Point")
      (libsource (lib "Test_Point") (part "TP_PCB?"))
    )
    (comp (ref "TP32")
      (value "~")
      (footprint "Test_Point")
      (description "Test_Point")
      (libsource (lib "") (part "TP_PCB?_1"))
    )
    (comp (ref "TP33")
      (value "Test_Point_PCB")
      (footprint "Test_Point")
      (description "Test_Point")
      (libsource (lib "Test_Point") (part "TP_PCB?"))
    )
    (comp (ref "TP34")
      (value "~")
      (footprint "Test_Point")
      (description "Test_Point")
      (libsource (lib "") (part "TP_PCB?_1"))
    )
    (comp (ref "TP35")
      (value "Test_Point_PCB")
      (footprint "Test_Point")
      (description "Test_Point")
      (libsource (lib "Connectors") (part "TP_PCB?"))
    )
    (comp (ref "TP36")
      (value "Test_Point_PCB")
      (footprint "Test_Point")
      (description "Test_Point")
      (libsource (lib "Connectors") (part "TP_PCB?"))
    )
    (comp (ref "TP37")
      (value "Test_Point_PCB")
      (footprint "Test_Point")
      (description "Test_Point")
      (libsource (lib "Connectors") (part "TP_PCB?"))
    )
    (comp (ref "TP38")
      (value "Test_Point_PCB")
      (footprint "Test_Point")
      (description "Test_Point")
      (libsource (lib "Connectors") (part "TP_PCB?"))
    )
    (comp (ref "TP39")
      (value "Test_Point_PCB")
      (footprint "Test_Point")
      (description "Test_Point")
      (libsource (lib "Connectors") (part "TP_PCB?"))
    )
    (comp (ref "TP41")
      (value "Test_Point_PCB")
      (footprint "Test_Point")
      (description "Test_Point")
      (libsource (lib "Connectors") (part "TP_PCB?"))
    )
    (comp (ref "TP42")
      (value "Test_Point_PCB")
      (footprint "Test_Point")
      (description "Test_Point")
      (libsource (lib "Connectors") (part "TP_PCB?"))
    )
    (comp (ref "TP43")
      (value "Test_Point_PCB")
      (footprint "Test_Point")
      (description "Test_Point")
      (libsource (lib "Connectors") (part "TP_PCB?"))
    )
    (comp (ref "TP44")
      (value "Test_Point_PCB")
      (footprint "Test_Point")
      (description "Test_Point")
      (libsource (lib "Connectors") (part "TP_PCB?"))
    )
    (comp (ref "TP45")
      (value "Test_Point_PCB")
      (footprint "Test_Point")
      (description "Test_Point")
      (libsource (lib "Connectors") (part "TP_PCB?"))
    )
    (comp (ref "TP46")
      (value "Test_Point_PCB")
      (footprint "Test_Point")
      (description "Test_Point")
      (libsource (lib "Connectors") (part "TP_PCB?"))
    )
    (comp (ref "TP47")
      (value "Test_Point_PCB")
      (footprint "Test_Point")
      (description "Test_Point")
      (libsource (lib "Connectors") (part "TP_PCB?"))
    )
    (comp (ref "TP48")
      (value "Test_Point_PCB")
      (footprint "Test_Point")
      (description "Test_Point")
      (libsource (lib "Connectors") (part "TP_PCB?"))
    )
    (comp (ref "TP49")
      (value "Test_Point_PCB")
      (footprint "Test_Point")
      (description "Test_Point")
      (libsource (lib "Connectors") (part "TP_PCB?"))
    )
    (comp (ref "TP50")
      (value "Test_Point_PCB")
      (footprint "Test_Point")
      (description "Test_Point")
      (libsource (lib "Connectors") (part "TP_PCB?"))
    )
    (comp (ref "TP51")
      (value "Test_Point_PCB")
      (footprint "Test_Point")
      (description "Test_Point")
      (libsource (lib "Connectors") (part "TP_PCB?"))
    )
    (comp (ref "TP52")
      (value "Test_Point_PCB")
      (footprint "Test_Point")
      (description "Test_Point")
      (libsource (lib "TEST_POINT") (part "TP_PCB?"))
    )
    (comp (ref "TP53")
      (value "Test_Point_PCB")
      (footprint "Test_Point")
      (description "Test_Point")
      (libsource (lib "TEST_POINT") (part "TP_PCB?"))
    )
    (comp (ref "U1")
      (value "LP2951-5.0")
      (footprint "SOIC-8_L")
      (libsource (lib "Integrated_Circuts") (part "LP2951-3.3"))
    )
    (comp (ref "U2")
      (value "B0505S-1W")
      (footprint "B0505S-1W")
      (libsource (lib "Integrated_Circuts") (part "B0505S-1W"))
    )
    (comp (ref "U3")
      (value "MC34063")
      (footprint "SOIC-8_M")
      (libsource (lib "Integrated_Circuts") (part "MC34063"))
    )
    (comp (ref "U4")
      (value "AMS1117")
      (footprint "SOT-89")
      (libsource (lib "Integrated_Circuts") (part "AMS1117"))
    )
    (comp (ref "U5")
      (value "MAX485")
      (footprint "SOIC-8-MFG")
      (libsource (lib "Integrated_Circuts") (part "MAX485"))
    )
    (comp (ref "U6")
      (value "ADUM1401BRWZ")
      (footprint "ADI-RW-16_M")
      (fields (field (name "MANUFACTURER") "Analog Devices"))
      (libsource (lib "Altium Content Vault") (part "ADI-ADUMX4X1-16"))
    )
    (comp (ref "U7")
      (value "STM32G030F6P6")
      (footprint "FP-TSSOP20-YA-IPC_A")
      (description "SOIC-20")
      (libsource (lib "Integrated_Circuts") (part "STM32G030F6P6"))
    )
    (comp (ref "U8")
      (value "AMS1117-3.3")
      (footprint "SOT-223")
      (libsource (lib "Integrated_Circuts") (part "AMS1117"))
    )
    (comp (ref "U9")
      (value "~")
      (footprint "SOT-23-5")
      (description "IC OPAMP GP 1 CIRCUIT SOT23-5")
      (fields (field (name "VOLTAGE") "6V"))
      (libsource (lib "Integrated_Circuts") (part "MCP6001T"))
    )
    (comp (ref "U10")
      (value "~")
      (footprint "SOT-23-5")
      (description "IC OPAMP GP 1 CIRCUIT SOT23-5")
      (fields (field (name "VOLTAGE") "6V"))
      (libsource (lib "Integrated_Circuts") (part "MCP6001T"))
    )
    (comp (ref "VD1") (value "SS16") (footprint "DO-214AC, SMA") (libsource (lib "DIODES") (part "DIODE")))
    (comp (ref "VD2") (value "SS16") (footprint "DO-214AC, SMA") (libsource (lib "DIODES") (part "DIODE")))
    (comp (ref "VD3") (value "1N4148") (footprint "SOD-123") (libsource (lib "DIODES") (part "DIODE")))
    (comp (ref "VD4") (value "1N4148") (footprint "SOD-123") (libsource (lib "DIODES") (part "DIODE")))
    (comp (ref "VD5") (value "1N4148") (footprint "SOD-123") (libsource (lib "DIODES") (part "DIODE")))
    (comp (ref "VD6") (value "1N4148") (footprint "SOD-123") (libsource (lib "DIODES") (part "DIODE")))
    (comp (ref "VD7") (value "SS16") (footprint "DO-214AC, SMA") (libsource (lib "DIODES") (part "DIODE")))
    (comp (ref "VD8") (value "SS16") (footprint "DO-214AC, SMA") (libsource (lib "DIODES") (part "DIODE")))
    (comp (ref "VD9") (value "1N4148") (footprint "SOD-123") (libsource (lib "DIODES") (part "DIODE")))
    (comp (ref "VD10") (value "1N4148") (footprint "SOD-123") (libsource (lib "DIODES") (part "DIODE")))
    (comp (ref "VD11") (value "1N4148") (footprint "SOD-123") (libsource (lib "DIODES") (part "DIODE")))
    (comp (ref "VD12") (value "1N4148") (footprint "SOD-123") (libsource (lib "DIODES") (part "DIODE")))
    (comp (ref "VD13") (value "DIODE") (footprint "DO-214AC, SMA") (libsource (lib "DIODES") (part "DIODE")))
    (comp (ref "VT1")
      (value "BC847")
      (footprint "SOT23-3")
      (libsource (lib "TRANSISTORS") (part "BIPOLAR-NPN-BEC"))
    )
    (comp (ref "VT2")
      (value "BC847")
      (footprint "SOT23-3")
      (libsource (lib "TRANSISTORS") (part "BIPOLAR-NPN-BEC"))
    )
    (comp (ref "X1")
      (value "CONN-4-PIN")
      (footprint "CONN-PLS-4-2.54mm_1")
      (libsource (lib "XH 4PIN") (part "CONN-4-PIN"))
    )
    (comp (ref "X2")
      (value "CONN-4-PIN")
      (footprint "CONN-PLS-4-2.54mm_1")
      (libsource (lib "XH 4PIN") (part "CONN-4-PIN"))
    )
    (comp (ref "X3") (value "CONN-2-PIN") (footprint "XH2-") (libsource (lib "XH 2PIN") (part "CONN-2-PIN")))
    (comp (ref "X4")
      (value "CONN-4-PIN")
      (footprint "CONN-PLS-4-2.54mm_1")
      (libsource (lib "XH 4PIN") (part "CONN-4-PIN"))
    )
    (comp (ref "X5")
      (value "CONN-4-PIN")
      (footprint "CONN-PLS-4-2.54mm_1")
      (libsource (lib "") (part "CONN-4-PIN_1"))
    )
    (comp (ref "X6") (value "CONN-2-PIN") (footprint "XH2-") (libsource (lib "XH 2PIN") (part "CONN-2-PIN")))
    (comp (ref "X7")
      (value "CONN-4-PIN")
      (footprint "CONN-PLS-4-2.54mm_1")
      (libsource (lib "XH 4PIN") (part "CONN-4-PIN"))
    )
    (comp (ref "X8")
      (value "CONN-4-PIN")
      (footprint "CONN-PLS-4-2.54mm_1")
      (libsource (lib "XH 4PIN") (part "CONN-4-PIN"))
    )
    (comp (ref "ZD1")
      (value "P6SMB16CA")
      (footprint "DO-214AA")
      (libsource (lib "P6SMB16CA") (part "P6SMB16CA"))
    )
    (comp (ref "ZD2")
      (value "P6SMB16CA")
      (footprint "DO-214AA")
      (libsource (lib "P6SMB16CA") (part "P6SMB16CA"))
    )
    (comp (ref "ZD3")
      (value "P6SMB16CA")
      (footprint "DO-214AA")
      (libsource (lib "P6SMB16CA") (part "P6SMB16CA"))
    )
  )
  (nets
    (net (code "1") (name "+3V3") (class "Default")
      (node (ref "C38") (pin "2") (pinfunction "2_2") (pintype "passive"))
      (node (ref "L5") (pin "1") (pinfunction "1_1") (pintype "passive"))
      (node (ref "R45") (pin "2") (pinfunction "2_2") (pintype "passive"))
      (node (ref "R48") (pin "2") (pinfunction "2_2") (pintype "passive"))
      (node (ref "TP35") (pin "1") (pinfunction "G9_1") (pintype "passive"))
      (node (ref "U6") (pin "1") (pinfunction "VDD1_1") (pintype "power_in"))
      (node (ref "U6") (pin "7") (pinfunction "VE1_7") (pintype "input"))
      (node (ref "U8") (pin "2") (pinfunction "VOUT_2") (pintype "passive"))
    )
    (net (code "2") (name "+3V3_MCU") (class "Default")
      (node (ref "C32") (pin "2") (pinfunction "2_2") (pintype "passive"))
      (node (ref "C33") (pin "1") (pinfunction "+_1") (pintype "passive"))
      (node (ref "C35") (pin "2") (pinfunction "2_2") (pintype "passive"))
      (node (ref "J1") (pin "1") (pinfunction "1_1") (pintype "passive"))
      (node (ref "L5") (pin "2") (pinfunction "2_2") (pintype "passive"))
      (node (ref "R58") (pin "1") (pinfunction "1_1") (pintype "passive"))
      (node (ref "TP34") (pin "1") (pinfunction "G9_1") (pintype "passive"))
      (node (ref "U7") (pin "4") (pinfunction "VDD/VDDA_4") (pintype "power_in"))
    )
    (net (code "3") (name "+5") (class "Default")
      (node (ref "C14") (pin "2") (pinfunction "2_2") (pintype "passive"))
      (node (ref "C15") (pin "2") (pinfunction "2_2") (pintype "passive"))
      (node (ref "C24") (pin "1") (pinfunction "+_1") (pintype "passive"))
      (node (ref "C36") (pin "2") (pinfunction "2_2") (pintype "passive"))
      (node (ref "C4") (pin "2") (pinfunction "2_2") (pintype "passive"))
      (node (ref "C45") (pin "2") (pinfunction "2_2") (pintype "passive"))
      (node (ref "C5") (pin "2") (pinfunction "2_2") (pintype "passive"))
      (node (ref "DD2") (pin "5") (pinfunction "VDD_5") (pintype "passive"))
      (node (ref "DD3") (pin "5") (pinfunction "VDD_5") (pintype "passive"))
      (node (ref "DD5") (pin "5") (pinfunction "VDD_5") (pintype "passive"))
      (node (ref "DD6") (pin "5") (pinfunction "VDD_5") (pintype "passive"))
      (node (ref "L1") (pin "2") (pinfunction "2_2") (pintype "passive"))
      (node (ref "L2") (pin "2") (pinfunction "2_2") (pintype "passive"))
      (node (ref "L6") (pin "1") (pinfunction "1_1") (pintype "passive"))
      (node (ref "U10") (pin "5") (pinfunction "VDD_5") (pintype "power_in"))
      (node (ref "U4") (pin "2") (pinfunction "VOUT_2") (pintype "passive"))
      (node (ref "U9") (pin "5") (pinfunction "VDD_5") (pintype "power_in"))
      (node (ref "X1") (pin "4") (pinfunction "4_4") (pintype "passive"))
      (node (ref "X4") (pin "2") (pinfunction "2_2") (pintype "passive"))
      (node (ref "X5") (pin "4") (pinfunction "4_4") (pintype "passive"))
      (node (ref "X8") (pin "2") (pinfunction "2_2") (pintype "passive"))
    )
    (net (code "4") (name "+5V_1") (class "Default")
      (node (ref "C21") (pin "1") (pinfunction "+_1") (pintype "passive"))
      (node (ref "C37") (pin "2") (pinfunction "2_2") (pintype "passive"))
      (node (ref "R43") (pin "1") (pinfunction "1_1") (pintype "passive"))
      (node (ref "U1") (pin "1") (pinfunction "OUT_1") (pintype "power_in"))
      (node (ref "U1") (pin "2") (pinfunction "SNS_2") (pintype "passive"))
      (node (ref "U8") (pin "3") (pinfunction "VIN_3") (pintype "power_in"))
    )
    (net (code "5") (name "+5V_ISO") (class "Default")
      (node (ref "C23") (pin "1") (pinfunction "1_1") (pintype "passive"))
      (node (ref "R44") (pin "2") (pinfunction "2_2") (pintype "passive"))
      (node (ref "R46") (pin "2") (pinfunction "2_2") (pintype "passive"))
      (node (ref "R47") (pin "2") (pinfunction "2_2") (pintype "passive"))
      (node (ref "TP23") (pin "1") (pinfunction "G9_1") (pintype "passive"))
      (node (ref "U2") (pin "4") (pinfunction "+Vo_4") (pintype "power_in"))
      (node (ref "U5") (pin "8") (pinfunction "VCC_8") (pintype "power_in"))
      (node (ref "U6") (pin "10") (pinfunction "VE2_10") (pintype "input"))
      (node (ref "U6") (pin "16") (pinfunction "VDD2_16") (pintype "power_in"))
    )
    (net (code "6") (name "+5V_RS") (class "Default")
      (node (ref "C22") (pin "2") (pinfunction "2_2") (pintype "passive"))
      (node (ref "C54") (pin "1") (pinfunction "+_1") (pintype "passive"))
      (node (ref "C55") (pin "2") (pinfunction "2_2") (pintype "passive"))
      (node (ref "L6") (pin "2") (pinfunction "2_2") (pintype "passive"))
      (node (ref "TP49") (pin "1") (pinfunction "G9_1") (pintype "passive"))
      (node (ref "U2") (pin "2") (pinfunction "VIN_2") (pintype "power_in"))
    )
    (net (code "7") (name "+24V") (class "Default")
      (node (ref "C1") (pin "1") (pinfunction "+_1") (pintype "passive"))
      (node (ref "C11") (pin "1") (pinfunction "+_1") (pintype "passive"))
      (node (ref "C17") (pin "2") (pinfunction "2_2") (pintype "passive"))
      (node (ref "C30") (pin "1") (pinfunction "+_1") (pintype "passive"))
      (node (ref "C31") (pin "1") (pinfunction "1_1") (pintype "passive"))
      (node (ref "C7") (pin "2") (pinfunction "2_2") (pintype "passive"))
      (node (ref "DD1") (pin "13") (pinfunction "VC_13") (pintype "passive"))
      (node (ref "DD1") (pin "15") (pinfunction "VCC_15") (pintype "passive"))
      (node (ref "DD4") (pin "13") (pinfunction "VC_13") (pintype "passive"))
      (node (ref "DD4") (pin "15") (pinfunction "VCC_15") (pintype "passive"))
      (node (ref "R49") (pin "1") (pinfunction "1_1") (pintype "passive"))
      (node (ref "U3") (pin "6") (pinfunction "VCC_6") (pintype "power_in"))
      (node (ref "X4") (pin "3") (pinfunction "3_3") (pintype "passive"))
      (node (ref "X8") (pin "3") (pinfunction "3_3") (pintype "passive"))
    )
    (net (code "8") (name "/ADC_1") (class "Default")
      (node (ref "R64") (pin "1") (pinfunction "1_1") (pintype "passive"))
      (node (ref "U7") (pin "7") (pinfunction "PA0_7") (pintype "bidirectional"))
    )
    (net (code "9") (name "/ADC_2") (class "Default")
      (node (ref "R74") (pin "1") (pinfunction "1_1") (pintype "passive"))
      (node (ref "U7") (pin "8") (pinfunction "PA1_8") (pintype "bidirectional"))
    )
    (net (code "10") (name "/ADC_3") (class "Default")
      (node (ref "C52") (pin "2") (pinfunction "2_2") (pintype "passive"))
      (node (ref "R70") (pin "2") (pinfunction "2_2") (pintype "passive"))
      (node (ref "R83") (pin "2") (pinfunction "2_2") (pintype "passive"))
      (node (ref "TP43") (pin "1") (pinfunction "G9_1") (pintype "passive"))
      (node (ref "U7") (pin "9") (pinfunction "PA2_9") (pintype "bidirectional"))
    )
    (net (code "11") (name "/ADC_4") (class "Default")
      (node (ref "C50") (pin "2") (pinfunction "2_2") (pintype "passive"))
      (node (ref "R77") (pin "2") (pinfunction "2_2") (pintype "passive"))
      (node (ref "R82") (pin "2") (pinfunction "2_2") (pintype "passive"))
      (node (ref "TP46") (pin "1") (pinfunction "G9_1") (pintype "passive"))
      (node (ref "U7") (pin "10") (pinfunction "PA3_10") (pintype "bidirectional"))
    )
    (net (code "12") (name "/ADC_I1") (class "Default")
      (node (ref "R70") (pin "1") (pinfunction "1_1") (pintype "passive"))
      (node (ref "X6") (pin "1") (pinfunction "1_1") (pintype "passive"))
    )
    (net (code "13") (name "/ADC_I2") (class "Default")
      (node (ref "R77") (pin "1") (pinfunction "1_1") (pintype "passive"))
      (node (ref "X3") (pin "1") (pinfunction "1_1") (pintype "passive"))
    )
    (net (code "14") (name "/DIRECT") (class "Default")
      (node (ref "R54") (pin "2") (pinfunction "2_2") (pintype "passive"))
      (node (ref "R55") (pin "2") (pinfunction "2_2") (pintype "passive"))
      (node (ref "TP27") (pin "1") (pinfunction "G9_1") (pintype "passive"))
      (node (ref "U6") (pin "5") (pinfunction "VIC_5") (pintype "input"))
      (node (ref "U7") (pin "2") (pinfunction "PB9/PC14-OSC32_IN_2") (pintype "bidirectional"))
    )
    (net (code "15") (name "/OUT_N1") (class "Default")
      (node (ref "C40") (pin "1") (pinfunction "1_1") (pintype "passive"))
      (node (ref "R66") (pin "1") (pinfunction "1_1") (pintype "passive"))
      (node (ref "TP41") (pin "1") (pinfunction "G9_1") (pintype "passive"))
      (node (ref "X5") (pin "2") (pinfunction "2_2") (pintype "passive"))
    )
    (net (code "16") (name "/OUT_N2") (class "Default")
      (node (ref "C47") (pin "1") (pinfunction "1_1") (pintype "passive"))
      (node (ref "R75") (pin "1") (pinfunction "1_1") (pintype "passive"))
      (node (ref "TP50") (pin "1") (pinfunction "G9_1") (pintype "passive"))
      (node (ref "X1") (pin "2") (pinfunction "2_2") (pintype "passive"))
    )
    (net (code "17") (name "/OUT_P1") (class "Default")
      (node (ref "C40") (pin "2") (pinfunction "2_2") (pintype "passive"))
      (node (ref "R60") (pin "1") (pinfunction "1_1") (pintype "passive"))
      (node (ref "TP36") (pin "1") (pinfunction "G9_1") (pintype "passive"))
      (node (ref "X5") (pin "3") (pinfunction "3_3") (pintype "passive"))
    )
    (net (code "18") (name "/OUT_P2") (class "Default")
      (node (ref "C47") (pin "2") (pinfunction "2_2") (pintype "passive"))
      (node (ref "R71") (pin "1") (pinfunction "1_1") (pintype "passive"))
      (node (ref "TP44") (pin "1") (pinfunction "G9_1") (pintype "passive"))
      (node (ref "X1") (pin "3") (pinfunction "3_3") (pintype "passive"))
    )
    (net (code "19") (name "/RX") (class "Default")
      (node (ref "J1") (pin "5") (pinfunction "5_5") (pintype "passive"))
      (node (ref "R45") (pin "1") (pinfunction "1_1") (pintype "passive"))
      (node (ref "TP31") (pin "1") (pinfunction "G9_1") (pintype "passive"))
      (node (ref "U6") (pin "6") (pinfunction "VOD_6") (pintype "tri_state"))
      (node (ref "U7") (pin "1") (pinfunction "PB7/PB8_1") (pintype "bidirectional"))
    )
    (net (code "20") (name "/SWCLC") (class "Default")
      (node (ref "J1") (pin "3") (pinfunction "3_3") (pintype "passive"))
      (node (ref "R61") (pin "1") (pinfunction "1_1") (pintype "passive"))
      (node (ref "U7") (pin "19") (pinfunction "PA15/PA14-BOOT0_19") (pintype "bidirectional"))
    )
    (net (code "21") (name "/SWDIO") (class "Default")
      (node (ref "J1") (pin "2") (pinfunction "2_2") (pintype "passive"))
      (node (ref "U7") (pin "18") (pinfunction "PA13_18") (pintype "bidirectional"))
    )
    (net (code "22") (name "/TX") (class "Default")
      (node (ref "J1") (pin "4") (pinfunction "4_4") (pintype "passive"))
      (node (ref "R48") (pin "1") (pinfunction "1_1") (pintype "passive"))
      (node (ref "TP28") (pin "1") (pinfunction "G9_1") (pintype "passive"))
      (node (ref "U6") (pin "4") (pinfunction "VIB_4") (pintype "input"))
      (node (ref "U7") (pin "20") (pinfunction "PB3/PB4/PB5/PB6_20") (pintype "bidirectional"))
    )
    (net (code "23") (name "GND") (class "Default")
      (node (ref "X1") (pin "1") (pinfunction "1_1") (pintype "passive"))
      (node (ref "X2") (pin "2") (pinfunction "2_2") (pintype "passive"))
      (node (ref "X2") (pin "3") (pinfunction "3_3") (pintype "passive"))
      (node (ref "X3") (pin "2") (pinfunction "2_2") (pintype "passive"))
      (node (ref "X4") (pin "4") (pinfunction "4_4") (pintype "passive"))
      (node (ref "X5") (pin "1") (pinfunction "1_1") (pintype "passive"))
      (node (ref "X6") (pin "2") (pinfunction "2_2") (pintype "passive"))
    )
    (net (code "24") (name "GND_2") (class "Default")
      (node (ref "C23") (pin "2") (pinfunction "2_2") (pintype "passive"))
      (node (ref "P1") (pin "2") (pinfunction "2_2") (pintype "passive"))
      (node (ref "R53") (pin "1") (pinfunction "1_1") (pintype "passive"))
      (node (ref "R56") (pin "1") (pinfunction "1_1") (pintype "passive"))
      (node (ref "TP33") (pin "1") (pinfunction "G9_1") (pintype "passive"))
      (node (ref "U2") (pin "3") (pinfunction "0V_3") (pintype "power_in"))
      (node (ref "U5") (pin "5") (pinfunction "GND_5") (pintype "power_in"))
      (node (ref "U6") (pin "15") (pinfunction "GND2_15") (pintype "power_in"))
      (node (ref "U6") (pin "9") (pinfunction "GND2_9") (pintype "power_in"))
      (node (ref "ZD2") (pin "1") (pinfunction "A_1") (pintype "passive"))
      (node (ref "ZD3") (pin "1") (pinfunction "A_1") (pintype "passive"))
    )
    (net (code "25") (name "GND_III") (class "Default")
      (node (ref "C1") (pin "2") (pinfunction "-_2") (pintype "passive"))
      (node (ref "C10") (pin "1") (pinfunction "1_1") (pintype "passive"))
      (node (ref "C11") (pin "2") (pinfunction "-_2") (pintype "passive"))
      (node (ref "C12") (pin "2") (pinfunction "2_2") (pintype "passive"))
      (node (ref "C13") (pin "2") (pinfunction "2_2") (pintype "passive"))
      (node (ref "C16") (pin "2") (pinfunction "2_2") (pintype "passive"))
      (node (ref "C17") (pin "1") (pinfunction "1_1") (pintype "passive"))
      (node (ref "C19") (pin "2") (pinfunction "2_2") (pintype "passive"))
      (node (ref "C2") (pin "2") (pinfunction "2_2") (pintype "passive"))
      (node (ref "C20") (pin "1") (pinfunction "1_1") (pintype "passive"))
      (node (ref "C21") (pin "2") (pinfunction "-_2") (pintype "passive"))
      (node (ref "C22") (pin "1") (pinfunction "1_1") (pintype "passive"))
      (node (ref "C24") (pin "2") (pinfunction "-_2") (pintype "passive"))
      (node (ref "C25") (pin "2") (pinfunction "2_2") (pintype "passive"))
      (node (ref "C26") (pin "2") (pinfunction "-_2") (pintype "passive"))
      (node (ref "C27") (pin "2") (pinfunction "-_2") (pintype "passive"))
      (node (ref "C28") (pin "2") (pinfunction "-_2") (pintype "passive"))
      (node (ref "C29") (pin "1") (pinfunction "1_1") (pintype "passive"))
      (node (ref "C3") (pin "2") (pinfunction "2_2") (pintype "passive"))
      (node (ref "C30") (pin "2") (pinfunction "-_2") (pintype "passive"))
      (node (ref "C31") (pin "2") (pinfunction "2_2") (pintype "passive"))
      (node (ref "C32") (pin "1") (pinfunction "1_1") (pintype "passive"))
      (node (ref "C33") (pin "2") (pinfunction "-_2") (pintype "passive"))
      (node (ref "C34") (pin "1") (pinfunction "1_1") (pintype "passive"))
      (node (ref "C35") (pin "1") (pinfunction "1_1") (pintype "passive"))
      (node (ref "C36") (pin "1") (pinfunction "1_1") (pintype "passive"))
      (node (ref "C37") (pin "1") (pinfunction "1_1") (pintype "passive"))
      (node (ref "C38") (pin "1") (pinfunction "1_1") (pintype "passive"))
      (node (ref "C41") (pin "1") (pinfunction "1_1") (pintype "passive"))
      (node (ref "C42") (pin "1") (pinfunction "1_1") (pintype "passive"))
      (node (ref "C43") (pin "1") (pinfunction "1_1") (pintype "passive"))
      (node (ref "C45") (pin "1") (pinfunction "1_1") (pintype "passive"))
      (node (ref "C48") (pin "1") (pinfunction "1_1") (pintype "passive"))
      (node (ref "C49") (pin "1") (pinfunction "1_1") (pintype "passive"))
      (node (ref "C50") (pin "1") (pinfunction "1_1") (pintype "passive"))
      (node (ref "C51") (pin "1") (pinfunction "1_1") (pintype "passive"))
      (node (ref "C52") (pin "1") (pinfunction "1_1") (pintype "passive"))
      (node (ref "C54") (pin "2") (pinfunction "-_2") (pintype "passive"))
      (node (ref "C55") (pin "1") (pinfunction "1_1") (pintype "passive"))
      (node (ref "C6") (pin "2") (pinfunction "2_2") (pintype "passive"))
      (node (ref "C7") (pin "1") (pinfunction "1_1") (pintype "passive"))
      (node (ref "C9") (pin "2") (pinfunction "2_2") (pintype "passive"))
      (node (ref "D2") (pin "2") (pinfunction "K_2") (pintype "passive"))
      (node (ref "D3") (pin "2") (pinfunction "K_2") (pintype "passive"))
      (node (ref "D4") (pin "2") (pinfunction "K_2") (pintype "passive"))
      (node (ref "DA2") (pin "3") (pinfunction "EMITTER_3") (pintype "passive"))
      (node (ref "DA4") (pin "3") (pinfunction "EMITTER_3") (pintype "passive"))
      (node (ref "DD1") (pin "12") (pinfunction "GND_12") (pintype "passive"))
      (node (ref "DD4") (pin "12") (pinfunction "GND_12") (pintype "passive"))
      (node (ref "J1") (pin "6") (pinfunction "6_6") (pintype "passive"))
      (node (ref "R1") (pin "1") (pinfunction "1_1") (pintype "passive"))
      (node (ref "R12") (pin "2") (pinfunction "2_2") (pintype "passive"))
      (node (ref "R16") (pin "2") (pinfunction "2_2") (pintype "passive"))
      (node (ref "R18") (pin "1") (pinfunction "1_1") (pintype "passive"))
      (node (ref "R2") (pin "1") (pinfunction "1_1") (pintype "passive"))
      (node (ref "R22") (pin "1") (pinfunction "1_1") (pintype "passive"))
      (node (ref "R23") (pin "1") (pinfunction "1_1") (pintype "passive"))
      (node (ref "R24") (pin "1") (pinfunction "1_1") (pintype "passive"))
      (node (ref "R28") (pin "2") (pinfunction "2_2") (pintype "passive"))
      (node (ref "R3") (pin "1") (pinfunction "1_1") (pintype "passive"))
      (node (ref "R30") (pin "1") (pinfunction "1_1") (pintype "passive"))
      (node (ref "R33") (pin "2") (pinfunction "2_2") (pintype "passive"))
      (node (ref "R37") (pin "2") (pinfunction "2_2") (pintype "passive"))
      (node (ref "R39") (pin "1") (pinfunction "1_1") (pintype "passive"))
      (node (ref "R55") (pin "1") (pinfunction "1_1") (pintype "passive"))
      (node (ref "R57") (pin "1") (pinfunction "1_1") (pintype "passive"))
      (node (ref "R61") (pin "2") (pinfunction "2_2") (pintype "passive"))
      (node (ref "R67") (pin "2") (pinfunction "2_2") (pintype "passive"))
      (node (ref "R68") (pin "1") (pinfunction "1_1") (pintype "passive"))
      (node (ref "R7") (pin "2") (pinfunction "2_2") (pintype "passive"))
      (node (ref "R76") (pin "2") (pinfunction "2_2") (pintype "passive"))
      (node (ref "R81") (pin "1") (pinfunction "1_1") (pintype "passive"))
      (node (ref "R82") (pin "1") (pinfunction "1_1") (pintype "passive"))
      (node (ref "R83") (pin "1") (pinfunction "1_1") (pintype "passive"))
      (node (ref "R9") (pin "1") (pinfunction "1_1") (pintype "passive"))
      (node (ref "TP3") (pin "1") (pinfunction "G9_1") (pintype "passive"))
      (node (ref "U1") (pin "3") (pinfunction "SD_3") (pintype "input"))
      (node (ref "U1") (pin "4") (pinfunction "GND_4") (pintype "power_in"))
      (node (ref "U10") (pin "2") (pinfunction "VSS_2") (pintype "power_in"))
      (node (ref "U2") (pin "1") (pinfunction "GND_1") (pintype "power_in"))
      (node (ref "U3") (pin "4") (pinfunction "GND_4") (pintype "power_in"))
      (node (ref "U4") (pin "1") (pinfunction "Ground_1") (pintype "power_in"))
      (node (ref "U6") (pin "2") (pinfunction "GND1_2") (pintype "power_in"))
      (node (ref "U6") (pin "8") (pinfunction "GND1_8") (pintype "power_in"))
      (node (ref "U7") (pin "5") (pinfunction "VSS/VSSA_5") (pintype "power_in"))
      (node (ref "U8") (pin "1") (pinfunction "Ground_1") (pintype "power_in"))
      (node (ref "U9") (pin "2") (pinfunction "VSS_2") (pintype "power_in"))
      (node (ref "VD11") (pin "1") (pinfunction "C_1") (pintype "passive"))
      (node (ref "VD12") (pin "2") (pinfunction "A_2") (pintype "passive"))
      (node (ref "VD13") (pin "2") (pinfunction "A_2") (pintype "passive"))
      (node (ref "VD5") (pin "1") (pinfunction "C_1") (pintype "passive"))
      (node (ref "VD6") (pin "2") (pinfunction "A_2") (pintype "passive"))
      (node (ref "VT1") (pin "3") (pinfunction "E_3") (pintype "passive"))
      (node (ref "VT2") (pin "3") (pinfunction "E_3") (pintype "passive"))
      (node (ref "X7") (pin "2") (pinfunction "2_2") (pintype "passive"))
      (node (ref "X7") (pin "3") (pinfunction "3_3") (pintype "passive"))
      (node (ref "X8") (pin "4") (pinfunction "4_4") (pintype "passive"))
    )
    (net (code "26") (name "Net-(C26-+)") (class "Default")
      (node (ref "C26") (pin "1") (pinfunction "+_1") (pintype "passive"))
      (node (ref "JE1") (pin "1") (pinfunction "1_1") (pintype "passive"))
      (node (ref "L4") (pin "1") (pinfunction "1_1") (pintype "passive"))
      (node (ref "U1") (pin "8") (pinfunction "IN_8") (pintype "power_in"))
    )
    (net (code "27") (name "Net-(C27-+)") (class "Default")
      (node (ref "C27") (pin "1") (pinfunction "+_1") (pintype "passive"))
      (node (ref "C29") (pin "2") (pinfunction "2_2") (pintype "passive"))
      (node (ref "L4") (pin "2") (pinfunction "2_2") (pintype "passive"))
      (node (ref "TP25") (pin "1") (pinfunction "G9_1") (pintype "passive"))
      (node (ref "U4") (pin "3") (pinfunction "VIN_3") (pintype "power_in"))
    )
    (net (code "28") (name "Net-(C28-+)") (class "Default")
      (node (ref "C28") (pin "1") (pinfunction "+_1") (pintype "passive"))
      (node (ref "JE1") (pin "2") (pinfunction "2_2") (pintype "passive"))
      (node (ref "L3") (pin "2") (pinfunction "2_2") (pintype "passive"))
      (node (ref "R52") (pin "1") (pinfunction "1_1") (pintype "passive"))
    )
    (net (code "29") (name "Net-(C41-Pad2)") (class "Default")
      (node (ref "C41") (pin "2") (pinfunction "2_2") (pintype "passive"))
      (node (ref "R62") (pin "1") (pinfunction "1_1") (pintype "passive"))
      (node (ref "R63") (pin "2") (pinfunction "2_2") (pintype "passive"))
    )
    (net (code "30") (name "Net-(C48-Pad2)") (class "Default")
      (node (ref "C48") (pin "2") (pinfunction "2_2") (pintype "passive"))
      (node (ref "R72") (pin "1") (pinfunction "1_1") (pintype "passive"))
      (node (ref "R73") (pin "2") (pinfunction "2_2") (pintype "passive"))
    )
    (net (code "31") (name "Net-(D2-A)") (class "Default")
      (node (ref "D2") (pin "1") (pinfunction "A_1") (pintype "passive"))
      (node (ref "R54") (pin "1") (pinfunction "1_1") (pintype "passive"))
    )
    (net (code "32") (name "Net-(D3-A)") (class "Default")
      (node (ref "D3") (pin "1") (pinfunction "A_1") (pintype "passive"))
      (node (ref "R59") (pin "2") (pinfunction "2_2") (pintype "passive"))
    )
    (net (code "33") (name "Net-(D4-A)") (class "Default")
      (node (ref "D4") (pin "1") (pinfunction "A_1") (pintype "passive"))
      (node (ref "R65") (pin "2") (pinfunction "2_2") (pintype "passive"))
    )
    (net (code "34") (name "Net-(DA1-CATHODE)") (class "Default")
      (node (ref "DA1") (pin "2") (pinfunction "CATHODE_2") (pintype "passive"))
      (node (ref "R1") (pin "2") (pinfunction "2_2") (pintype "passive"))
    )
    (net (code "35") (name "Net-(DA1-COLLECTOR)") (class "Default")
      (node (ref "C2") (pin "1") (pinfunction "1_1") (pintype "passive"))
      (node (ref "C6") (pin "1") (pinfunction "1_1") (pintype "passive"))
      (node (ref "DA1") (pin "4") (pinfunction "COLLECTOR_4") (pintype "passive"))
      (node (ref "DD1") (pin "1") (pinfunction "INV_IN_1") (pintype "passive"))
      (node (ref "R2") (pin "2") (pinfunction "2_2") (pintype "passive"))
      (node (ref "R20") (pin "2") (pinfunction "2_2") (pintype "passive"))
      (node (ref "TP1") (pin "1") (pinfunction "G9_1") (pintype "passive"))
    )
    (net (code "36") (name "Net-(DA1-EMITTER)") (class "Default")
      (node (ref "DA1") (pin "3") (pinfunction "EMITTER_3") (pintype "passive"))
      (node (ref "R3") (pin "2") (pinfunction "2_2") (pintype "passive"))
    )
    (net (code "37") (name "Net-(DA2-ANODE)") (class "Default")
      (node (ref "DA2") (pin "1") (pinfunction "ANODE_1") (pintype "passive"))
      (node (ref "R4") (pin "1") (pinfunction "1_1") (pintype "passive"))
    )
    (net (code "38") (name "Net-(DA2-CATHODE)") (class "Default")
      (node (ref "DA2") (pin "2") (pinfunction "CATHODE_2") (pintype "passive"))
      (node (ref "TP2") (pin "1") (pinfunction "G9_1") (pintype "passive"))
      (node (ref "VT1") (pin "2") (pinfunction "C_2") (pintype "passive"))
    )
    (net (code "39") (name "Net-(DA3-CATHODE)") (class "Default")
      (node (ref "DA3") (pin "2") (pinfunction "CATHODE_2") (pintype "passive"))
      (node (ref "R22") (pin "2") (pinfunction "2_2") (pintype "passive"))
    )
    (net (code "40") (name "Net-(DA3-COLLECTOR)") (class "Default")
      (node (ref "C12") (pin "1") (pinfunction "1_1") (pintype "passive"))
      (node (ref "C16") (pin "1") (pinfunction "1_1") (pintype "passive"))
      (node (ref "DA3") (pin "4") (pinfunction "COLLECTOR_4") (pintype "passive"))
      (node (ref "DD4") (pin "1") (pinfunction "INV_IN_1") (pintype "passive"))
      (node (ref "R23") (pin "2") (pinfunction "2_2") (pintype "passive"))
      (node (ref "R41") (pin "2") (pinfunction "2_2") (pintype "passive"))
      (node (ref "TP12") (pin "1") (pinfunction "G9_1") (pintype "passive"))
    )
    (net (code "41") (name "Net-(DA3-EMITTER)") (class "Default")
      (node (ref "DA3") (pin "3") (pinfunction "EMITTER_3") (pintype "passive"))
      (node (ref "R24") (pin "2") (pinfunction "2_2") (pintype "passive"))
    )
    (net (code "42") (name "Net-(DA4-ANODE)") (class "Default")
      (node (ref "DA4") (pin "1") (pinfunction "ANODE_1") (pintype "passive"))
      (node (ref "R25") (pin "1") (pinfunction "1_1") (pintype "passive"))
    )
    (net (code "43") (name "Net-(DA4-CATHODE)") (class "Default")
      (node (ref "DA4") (pin "2") (pinfunction "CATHODE_2") (pintype "passive"))
      (node (ref "TP13") (pin "1") (pinfunction "G9_1") (pintype "passive"))
      (node (ref "VT2") (pin "2") (pinfunction "C_2") (pintype "passive"))
    )
    (net (code "44") (name "Net-(DD1-COMPENSATION)") (class "Default")
      (node (ref "DD1") (pin "9") (pinfunction "COMPENSATION_9") (pintype "passive"))
      (node (ref "R20") (pin "1") (pinfunction "1_1") (pintype "passive"))
    )
    (net (code "45") (name "Net-(DD1-CT)") (class "Default")
      (node (ref "DD1") (pin "5") (pinfunction "CT_5") (pintype "passive"))
      (node (ref "R14") (pin "1") (pinfunction "1_1") (pintype "passive"))
    )
    (net (code "46") (name "Net-(DD1-DISCHARGE)") (class "Default")
      (node (ref "DD1") (pin "7") (pinfunction "DISCHARGE_7") (pintype "passive"))
      (node (ref "R17") (pin "1") (pinfunction "1_1") (pintype "passive"))
    )
    (net (code "47") (name "Net-(DD1-NON_INV_IN)") (class "Default")
      (node (ref "DD1") (pin "2") (pinfunction "NON_INV_IN_2") (pintype "passive"))
      (node (ref "R7") (pin "1") (pinfunction "1_1") (pintype "passive"))
      (node (ref "R8") (pin "2") (pinfunction "2_2") (pintype "passive"))
      (node (ref "TP8") (pin "1") (pinfunction "G9_1") (pintype "passive"))
    )
    (net (code "48") (name "Net-(DD1-RT)") (class "Default")
      (node (ref "DD1") (pin "6") (pinfunction "RT_6") (pintype "passive"))
      (node (ref "R16") (pin "1") (pinfunction "1_1") (pintype "passive"))
    )
    (net (code "49") (name "Net-(DD1-SHUT_DOWN)") (class "Default")
      (node (ref "C10") (pin "2") (pinfunction "2_2") (pintype "passive"))
      (node (ref "DD1") (pin "10") (pinfunction "SHUT_DOWN_10") (pintype "passive"))
      (node (ref "R15") (pin "1") (pinfunction "1_1") (pintype "passive"))
      (node (ref "R18") (pin "2") (pinfunction "2_2") (pintype "passive"))
    )
    (net (code "50") (name "Net-(DD1-SOFT_START)") (class "Default")
      (node (ref "C9") (pin "1") (pinfunction "1_1") (pintype "passive"))
      (node (ref "DD1") (pin "8") (pinfunction "SOFT_START_8") (pintype "passive"))
    )
    (net (code "51") (name "Net-(DD1-SYNC)") (class "Default")
      (node (ref "DD1") (pin "3") (pinfunction "SYNC_3") (pintype "passive"))
      (node (ref "R12") (pin "1") (pinfunction "1_1") (pintype "passive"))
    )
    (net (code "52") (name "Net-(DD1-V_REF)") (class "Default")
      (node (ref "C3") (pin "1") (pinfunction "1_1") (pintype "passive"))
      (node (ref "DD1") (pin "16") (pinfunction "V_REF_16") (pintype "passive"))
      (node (ref "R2") (pin "3") (pinfunction "3_3") (pintype "passive"))
      (node (ref "R8") (pin "1") (pinfunction "1_1") (pintype "passive"))
    )
    (net (code "53") (name "Net-(DD2-VIN-)") (class "Default")
      (node (ref "DD2") (pin "4") (pinfunction "VIN-_4") (pintype "passive"))
      (node (ref "R11") (pin "2") (pinfunction "2_2") (pintype "passive"))
      (node (ref "R13") (pin "1") (pinfunction "1_1") (pintype "passive"))
    )
    (net (code "54") (name "Net-(DD2-VOUT)") (class "Default")
      (node (ref "DD2") (pin "1") (pinfunction "VOUT_1") (pintype "passive"))
      (node (ref "R11") (pin "1") (pinfunction "1_1") (pintype "passive"))
      (node (ref "R6") (pin "1") (pinfunction "1_1") (pintype "passive"))
    )
    (net (code "55") (name "Net-(DD2-VSS)") (class "Default")
      (node (ref "C4") (pin "1") (pinfunction "1_1") (pintype "passive"))
      (node (ref "C5") (pin "1") (pinfunction "1_1") (pintype "passive"))
      (node (ref "C8") (pin "2") (pinfunction "2_2") (pintype "passive"))
      (node (ref "DD2") (pin "2") (pinfunction "VSS_2") (pintype "passive"))
      (node (ref "DD3") (pin "2") (pinfunction "VSS_2") (pintype "passive"))
      (node (ref "R13") (pin "2") (pinfunction "2_2") (pintype "passive"))
      (node (ref "R21") (pin "2") (pinfunction "2_2") (pintype "passive"))
      (node (ref "VD3") (pin "2") (pinfunction "A_2") (pintype "passive"))
      (node (ref "VD4") (pin "1") (pinfunction "C_1") (pintype "passive"))
    )
    (net (code "56") (name "Net-(DD3-VIN+)") (class "Default")
      (node (ref "C8") (pin "1") (pinfunction "1_1") (pintype "passive"))
      (node (ref "DD3") (pin "3") (pinfunction "VIN+_3") (pintype "passive"))
      (node (ref "R10") (pin "2") (pinfunction "2_2") (pintype "passive"))
      (node (ref "TP9") (pin "1") (pinfunction "G9_1") (pintype "passive"))
      (node (ref "VD1") (pin "2") (pinfunction "A_2") (pintype "passive"))
      (node (ref "VD2") (pin "2") (pinfunction "A_2") (pintype "passive"))
    )
    (net (code "57") (name "Net-(DD3-VIN-)") (class "Default")
      (node (ref "DD3") (pin "4") (pinfunction "VIN-_4") (pintype "passive"))
      (node (ref "R19") (pin "2") (pinfunction "2_2") (pintype "passive"))
      (node (ref "R21") (pin "1") (pinfunction "1_1") (pintype "passive"))
    )
    (net (code "58") (name "Net-(DD3-VOUT)") (class "Default")
      (node (ref "DD3") (pin "1") (pinfunction "VOUT_1") (pintype "passive"))
      (node (ref "R14") (pin "2") (pinfunction "2_2") (pintype "passive"))
      (node (ref "R19") (pin "1") (pinfunction "1_1") (pintype "passive"))
      (node (ref "TP6") (pin "1") (pinfunction "G9_1") (pintype "passive"))
    )
    (net (code "59") (name "Net-(DD4-COMPENSATION)") (class "Default")
      (node (ref "DD4") (pin "9") (pinfunction "COMPENSATION_9") (pintype "passive"))
      (node (ref "R41") (pin "1") (pinfunction "1_1") (pintype "passive"))
    )
    (net (code "60") (name "Net-(DD4-CT)") (class "Default")
      (node (ref "DD4") (pin "5") (pinfunction "CT_5") (pintype "passive"))
      (node (ref "R35") (pin "1") (pinfunction "1_1") (pintype "passive"))
    )
    (net (code "61") (name "Net-(DD4-DISCHARGE)") (class "Default")
      (node (ref "DD4") (pin "7") (pinfunction "DISCHARGE_7") (pintype "passive"))
      (node (ref "R38") (pin "1") (pinfunction "1_1") (pintype "passive"))
    )
    (net (code "62") (name "Net-(DD4-NON_INV_IN)") (class "Default")
      (node (ref "DD4") (pin "2") (pinfunction "NON_INV_IN_2") (pintype "passive"))
      (node (ref "R28") (pin "1") (pinfunction "1_1") (pintype "passive"))
      (node (ref "R29") (pin "2") (pinfunction "2_2") (pintype "passive"))
      (node (ref "TP19") (pin "1") (pinfunction "G9_1") (pintype "passive"))
    )
    (net (code "63") (name "Net-(DD4-RT)") (class "Default")
      (node (ref "DD4") (pin "6") (pinfunction "RT_6") (pintype "passive"))
      (node (ref "R37") (pin "1") (pinfunction "1_1") (pintype "passive"))
    )
    (net (code "64") (name "Net-(DD4-SHUT_DOWN)") (class "Default")
      (node (ref "C20") (pin "2") (pinfunction "2_2") (pintype "passive"))
      (node (ref "DD4") (pin "10") (pinfunction "SHUT_DOWN_10") (pintype "passive"))
      (node (ref "R36") (pin "1") (pinfunction "1_1") (pintype "passive"))
      (node (ref "R39") (pin "2") (pinfunction "2_2") (pintype "passive"))
    )
    (net (code "65") (name "Net-(DD4-SOFT_START)") (class "Default")
      (node (ref "C19") (pin "1") (pinfunction "1_1") (pintype "passive"))
      (node (ref "DD4") (pin "8") (pinfunction "SOFT_START_8") (pintype "passive"))
    )
    (net (code "66") (name "Net-(DD4-SYNC)") (class "Default")
      (node (ref "DD4") (pin "3") (pinfunction "SYNC_3") (pintype "passive"))
      (node (ref "R33") (pin "1") (pinfunction "1_1") (pintype "passive"))
    )
    (net (code "67") (name "Net-(DD4-V_REF)") (class "Default")
      (node (ref "C13") (pin "1") (pinfunction "1_1") (pintype "passive"))
      (node (ref "DD4") (pin "16") (pinfunction "V_REF_16") (pintype "passive"))
      (node (ref "R23") (pin "3") (pinfunction "3_3") (pintype "passive"))
      (node (ref "R29") (pin "1") (pinfunction "1_1") (pintype "passive"))
    )
    (net (code "68") (name "Net-(DD5-VIN-)") (class "Default")
      (node (ref "DD5") (pin "4") (pinfunction "VIN-_4") (pintype "passive"))
      (node (ref "R32") (pin "2") (pinfunction "2_2") (pintype "passive"))
      (node (ref "R34") (pin "1") (pinfunction "1_1") (pintype "passive"))
    )
    (net (code "69") (name "Net-(DD5-VOUT)") (class "Default")
      (node (ref "DD5") (pin "1") (pinfunction "VOUT_1") (pintype "passive"))
      (node (ref "R27") (pin "1") (pinfunction "1_1") (pintype "passive"))
      (node (ref "R32") (pin "1") (pinfunction "1_1") (pintype "passive"))
    )
    (net (code "70") (name "Net-(DD5-VSS)") (class "Default")
      (node (ref "C14") (pin "1") (pinfunction "1_1") (pintype "passive"))
      (node (ref "C15") (pin "1") (pinfunction "1_1") (pintype "passive"))
      (node (ref "C18") (pin "2") (pinfunction "2_2") (pintype "passive"))
      (node (ref "DD5") (pin "2") (pinfunction "VSS_2") (pintype "passive"))
      (node (ref "DD6") (pin "2") (pinfunction "VSS_2") (pintype "passive"))
      (node (ref "R34") (pin "2") (pinfunction "2_2") (pintype "passive"))
      (node (ref "R42") (pin "2") (pinfunction "2_2") (pintype "passive"))
      (node (ref "VD10") (pin "1") (pinfunction "C_1") (pintype "passive"))
      (node (ref "VD9") (pin "2") (pinfunction "A_2") (pintype "passive"))
    )
    (net (code "71") (name "Net-(DD6-VIN+)") (class "Default")
      (node (ref "C18") (pin "1") (pinfunction "1_1") (pintype "passive"))
      (node (ref "DD6") (pin "3") (pinfunction "VIN+_3") (pintype "passive"))
      (node (ref "R31") (pin "2") (pinfunction "2_2") (pintype "passive"))
      (node (ref "TP20") (pin "1") (pinfunction "G9_1") (pintype "passive"))
      (node (ref "VD7") (pin "2") (pinfunction "A_2") (pintype "passive"))
      (node (ref "VD8") (pin "2") (pinfunction "A_2") (pintype "passive"))
    )
    (net (code "72") (name "Net-(DD6-VIN-)") (class "Default")
      (node (ref "DD6") (pin "4") (pinfunction "VIN-_4") (pintype "passive"))
      (node (ref "R40") (pin "2") (pinfunction "2_2") (pintype "passive"))
      (node (ref "R42") (pin "1") (pinfunction "1_1") (pintype "passive"))
    )
    (net (code "73") (name "Net-(DD6-VOUT)") (class "Default")
      (node (ref "DD6") (pin "1") (pinfunction "VOUT_1") (pintype "passive"))
      (node (ref "R35") (pin "2") (pinfunction "2_2") (pintype "passive"))
      (node (ref "R40") (pin "1") (pinfunction "1_1") (pintype "passive"))
      (node (ref "TP17") (pin "1") (pinfunction "G9_1") (pintype "passive"))
    )
    (net (code "74") (name "Net-(L1-Pad1)") (class "Default")
      (node (ref "L1") (pin "1") (pinfunction "1_1") (pintype "passive"))
      (node (ref "R4") (pin "2") (pinfunction "2_2") (pintype "passive"))
    )
    (net (code "75") (name "Net-(L2-Pad1)") (class "Default")
      (node (ref "L2") (pin "1") (pinfunction "1_1") (pintype "passive"))
      (node (ref "R25") (pin "2") (pinfunction "2_2") (pintype "passive"))
    )
    (net (code "76") (name "Net-(TP5-G9)") (class "Default")
      (node (ref "R10") (pin "1") (pinfunction "1_1") (pintype "passive"))
      (node (ref "R6") (pin "2") (pinfunction "2_2") (pintype "passive"))
      (node (ref "R6") (pin "3") (pinfunction "3_3") (pintype "passive"))
      (node (ref "TP5") (pin "1") (pinfunction "G9_1") (pintype "passive"))
      (node (ref "VD1") (pin "1") (pinfunction "C_1") (pintype "passive"))
    )
    (net (code "77") (name "Net-(TP11-G9)") (class "Default")
      (node (ref "R17") (pin "2") (pinfunction "2_2") (pintype "passive"))
      (node (ref "TP11") (pin "1") (pinfunction "G9_1") (pintype "passive"))
      (node (ref "VD2") (pin "1") (pinfunction "C_1") (pintype "passive"))
    )
    (net (code "78") (name "Net-(TP16-G9)") (class "Default")
      (node (ref "R27") (pin "2") (pinfunction "2_2") (pintype "passive"))
      (node (ref "R27") (pin "3") (pinfunction "3_3") (pintype "passive"))
      (node (ref "R31") (pin "1") (pinfunction "1_1") (pintype "passive"))
      (node (ref "TP16") (pin "1") (pinfunction "G9_1") (pintype "passive"))
      (node (ref "VD7") (pin "1") (pinfunction "C_1") (pintype "passive"))
    )
    (net (code "79") (name "Net-(TP22-G9)") (class "Default")
      (node (ref "R38") (pin "2") (pinfunction "2_2") (pintype "passive"))
      (node (ref "TP22") (pin "1") (pinfunction "G9_1") (pintype "passive"))
      (node (ref "VD8") (pin "1") (pinfunction "C_1") (pintype "passive"))
    )
    (net (code "80") (name "Net-(TP24-G9)") (class "Default")
      (node (ref "L3") (pin "1") (pinfunction "1_1") (pintype "passive"))
      (node (ref "TP24") (pin "1") (pinfunction "G9_1") (pintype "passive"))
      (node (ref "U3") (pin "2") (pinfunction "SWE_2") (pintype "open_emitter"))
      (node (ref "VD13") (pin "1") (pinfunction "C_1") (pintype "passive"))
    )
    (net (code "81") (name "Net-(TP26-G9)") (class "Default")
      (node (ref "R46") (pin "1") (pinfunction "1_1") (pintype "passive"))
      (node (ref "R50") (pin "1") (pinfunction "1_1") (pintype "passive"))
      (node (ref "TP26") (pin "1") (pinfunction "G9_1") (pintype "passive"))
      (node (ref "U5") (pin "4") (pinfunction "DI_4") (pintype "input"))
    )
    (net (code "82") (name "Net-(TP30-G9)") (class "Default")
      (node (ref "R53") (pin "2") (pinfunction "2_2") (pintype "passive"))
      (node (ref "TP30") (pin "1") (pinfunction "G9_1") (pintype "passive"))
      (node (ref "U5") (pin "2") (pinfunction "~{RE}_2") (pintype "input"))
      (node (ref "U5") (pin "3") (pinfunction "DE_3") (pintype "input"))
      (node (ref "U6") (pin "12") (pinfunction "VOC_12") (pintype "tri_state"))
    )
    (net (code "83") (name "Net-(TP32-G9)") (class "Default")
      (node (ref "R47") (pin "1") (pinfunction "1_1") (pintype "passive"))
      (node (ref "R51") (pin "1") (pinfunction "1_1") (pintype "passive"))
      (node (ref "TP32") (pin "1") (pinfunction "G9_1") (pintype "passive"))
      (node (ref "U5") (pin "1") (pinfunction "RO_1") (pintype "output"))
    )
    (net (code "84") (name "Net-(TP37-G9)") (class "Default")
      (node (ref "C39") (pin "2") (pinfunction "2_2") (pintype "passive"))
      (node (ref "C43") (pin "2") (pinfunction "2_2") (pintype "passive"))
      (node (ref "R60") (pin "2") (pinfunction "2_2") (pintype "passive"))
      (node (ref "R68") (pin "2") (pinfunction "2_2") (pintype "passive"))
      (node (ref "TP37") (pin "1") (pinfunction "G9_1") (pintype "passive"))
      (node (ref "U9") (pin "3") (pinfunction "VIN+_3") (pintype "input"))
    )
    (net (code "85") (name "Net-(TP38-G9)") (class "Default")
      (node (ref "C42") (pin "2") (pinfunction "2_2") (pintype "passive"))
      (node (ref "R63") (pin "1") (pinfunction "1_1") (pintype "passive"))
      (node (ref "R64") (pin "2") (pinfunction "2_2") (pintype "passive"))
      (node (ref "R67") (pin "1") (pinfunction "1_1") (pintype "passive"))
      (node (ref "TP38") (pin "1") (pinfunction "G9_1") (pintype "passive"))
    )
    (net (code "86") (name "Net-(TP39-G9)") (class "Default")
      (node (ref "C44") (pin "2") (pinfunction "2_2") (pintype "passive"))
      (node (ref "R62") (pin "2") (pinfunction "2_2") (pintype "passive"))
      (node (ref "R69") (pin "2") (pinfunction "2_2") (pintype "passive"))
      (node (ref "TP39") (pin "1") (pinfunction "G9_1") (pintype "passive"))
      (node (ref "U9") (pin "1") (pinfunction "VOUT_1") (pintype "output"))
    )
    (net (code "87") (name "Net-(TP42-G9)") (class "Default")
      (node (ref "C39") (pin "1") (pinfunction "1_1") (pintype "passive"))
      (node (ref "C44") (pin "1") (pinfunction "1_1") (pintype "passive"))
      (node (ref "R66") (pin "2") (pinfunction "2_2") (pintype "passive"))
      (node (ref "R69") (pin "1") (pinfunction "1_1") (pintype "passive"))
      (node (ref "TP42") (pin "1") (pinfunction "G9_1") (pintype "passive"))
      (node (ref "U9") (pin "4") (pinfunction "VIN-_4") (pintype "input"))
    )
    (net (code "88") (name "Net-(TP45-G9)") (class "Default")
      (node (ref "C46") (pin "2") (pinfunction "2_2") (pintype "passive"))
      (node (ref "C51") (pin "2") (pinfunction "2_2") (pintype "passive"))
      (node (ref "R71") (pin "2") (pinfunction "2_2") (pintype "passive"))
      (node (ref "R81") (pin "2") (pinfunction "2_2") (pintype "passive"))
      (node (ref "TP45") (pin "1") (pinfunction "G9_1") (pintype "passive"))
      (node (ref "U10") (pin "3") (pinfunction "VIN+_3") (pintype "input"))
    )
    (net (code "89") (name "Net-(TP47-G9)") (class "Default")
      (node (ref "C49") (pin "2") (pinfunction "2_2") (pintype "passive"))
      (node (ref "R73") (pin "1") (pinfunction "1_1") (pintype "passive"))
      (node (ref "R74") (pin "2") (pinfunction "2_2") (pintype "passive"))
      (node (ref "R76") (pin "1") (pinfunction "1_1") (pintype "passive"))
      (node (ref "TP47") (pin "1") (pinfunction "G9_1") (pintype "passive"))
    )
    (net (code "90") (name "Net-(TP48-G9)") (class "Default")
      (node (ref "C53") (pin "2") (pinfunction "2_2") (pintype "passive"))
      (node (ref "R72") (pin "2") (pinfunction "2_2") (pintype "passive"))
      (node (ref "R84") (pin "2") (pinfunction "2_2") (pintype "passive"))
      (node (ref "TP48") (pin "1") (pinfunction "G9_1") (pintype "passive"))
      (node (ref "U10") (pin "1") (pinfunction "VOUT_1") (pintype "output"))
    )
    (net (code "91") (name "Net-(TP51-G9)") (class "Default")
      (node (ref "C46") (pin "1") (pinfunction "1_1") (pintype "passive"))
      (node (ref "C53") (pin "1") (pinfunction "1_1") (pintype "passive"))
      (node (ref "R75") (pin "2") (pinfunction "2_2") (pintype "passive"))
      (node (ref "R84") (pin "1") (pinfunction "1_1") (pintype "passive"))
      (node (ref "TP51") (pin "1") (pinfunction "G9_1") (pintype "passive"))
      (node (ref "U10") (pin "4") (pinfunction "VIN-_4") (pintype "input"))
    )
    (net (code "92") (name "Net-(U1-FB)") (class "Default")
      (node (ref "U1") (pin "6") (pinfunction "VTAP_6") (pintype "passive"))
      (node (ref "U1") (pin "7") (pinfunction "FB_7") (pintype "input"))
    )
    (net (code "93") (name "Net-(U1-~{ERR})") (class "Default")
      (node (ref "R43") (pin "2") (pinfunction "2_2") (pintype "passive"))
      (node (ref "U1") (pin "5") (pinfunction "~{ERR}_5") (pintype "open_collector"))
    )
    (net (code "94") (name "Net-(U3-CII)") (class "Default")
      (node (ref "R52") (pin "2") (pinfunction "2_2") (pintype "passive"))
      (node (ref "R57") (pin "2") (pinfunction "2_2") (pintype "passive"))
      (node (ref "U3") (pin "5") (pinfunction "CII_5") (pintype "input"))
    )
    (net (code "95") (name "Net-(U3-DRC)") (class "Default")
      (node (ref "R49") (pin "2") (pinfunction "2_2") (pintype "passive"))
      (node (ref "U3") (pin "1") (pinfunction "SWC_1") (pintype "open_collector"))
      (node (ref "U3") (pin "7") (pinfunction "IPK_7") (pintype "passive"))
      (node (ref "U3") (pin "8") (pinfunction "DRC_8") (pintype "open_collector"))
    )
    (net (code "96") (name "Net-(U3-TC)") (class "Default")
      (node (ref "C25") (pin "1") (pinfunction "1_1") (pintype "passive"))
      (node (ref "U3") (pin "3") (pinfunction "TC_3") (pintype "passive"))
    )
    (net (code "97") (name "Net-(U5-A)") (class "Default")
      (node (ref "P1") (pin "3") (pinfunction "3_3") (pintype "passive"))
      (node (ref "R44") (pin "1") (pinfunction "1_1") (pintype "passive"))
      (node (ref "U5") (pin "6") (pinfunction "A_6") (pintype "bidirectional"))
      (node (ref "ZD1") (pin "2") (pinfunction "A_2") (pintype "passive"))
      (node (ref "ZD2") (pin "2") (pinfunction "A_2") (pintype "passive"))
    )
    (net (code "98") (name "Net-(U5-B)") (class "Default")
      (node (ref "P1") (pin "1") (pinfunction "1_1") (pintype "passive"))
      (node (ref "R56") (pin "2") (pinfunction "2_2") (pintype "passive"))
      (node (ref "U5") (pin "7") (pinfunction "B_7") (pintype "bidirectional"))
      (node (ref "ZD1") (pin "1") (pinfunction "A_1") (pintype "passive"))
      (node (ref "ZD3") (pin "2") (pinfunction "A_2") (pintype "passive"))
    )
    (net (code "99") (name "Net-(U6-VID)") (class "Default")
      (node (ref "R51") (pin "2") (pinfunction "2_2") (pintype "passive"))
      (node (ref "U6") (pin "11") (pinfunction "VID_11") (pintype "input"))
    )
    (net (code "100") (name "Net-(U6-VOB)") (class "Default")
      (node (ref "R50") (pin "2") (pinfunction "2_2") (pintype "passive"))
      (node (ref "U6") (pin "13") (pinfunction "VOB_13") (pintype "tri_state"))
    )
    (net (code "101") (name "Net-(U7-PA12[PA10])") (class "Default")
      (node (ref "R59") (pin "1") (pinfunction "1_1") (pintype "passive"))
      (node (ref "U7") (pin "17") (pinfunction "PA12[PA10]_17") (pintype "bidirectional"))
    )
    (net (code "102") (name "Net-(U7-PC15-OSC32_OUT)") (class "Default")
      (node (ref "R65") (pin "1") (pinfunction "1_1") (pintype "passive"))
      (node (ref "U7") (pin "3") (pinfunction "PC15-OSC32_OUT_3") (pintype "bidirectional"))
    )
    (net (code "103") (name "Net-(U7-~{RST})") (class "Default")
      (node (ref "C34") (pin "2") (pinfunction "2_2") (pintype "passive"))
      (node (ref "R58") (pin "2") (pinfunction "2_2") (pintype "passive"))
      (node (ref "U7") (pin "6") (pinfunction "~{RST}_6") (pintype "input"))
    )
    (net (code "104") (name "Net-(VD3-C)") (class "Default")
      (node (ref "VD3") (pin "1") (pinfunction "C_1") (pintype "passive"))
      (node (ref "VD5") (pin "2") (pinfunction "A_2") (pintype "passive"))
    )
    (net (code "105") (name "Net-(VD4-A)") (class "Default")
      (node (ref "VD4") (pin "2") (pinfunction "A_2") (pintype "passive"))
      (node (ref "VD6") (pin "1") (pinfunction "C_1") (pintype "passive"))
    )
    (net (code "106") (name "Net-(VD10-A)") (class "Default")
      (node (ref "VD10") (pin "2") (pinfunction "A_2") (pintype "passive"))
      (node (ref "VD12") (pin "1") (pinfunction "C_1") (pintype "passive"))
    )
    (net (code "107") (name "Net-(VD11-A)") (class "Default")
      (node (ref "VD11") (pin "2") (pinfunction "A_2") (pintype "passive"))
      (node (ref "VD9") (pin "1") (pinfunction "C_1") (pintype "passive"))
    )
    (net (code "108") (name "Net-(VT1-B)") (class "Default")
      (node (ref "R5") (pin "2") (pinfunction "2_2") (pintype "passive"))
      (node (ref "VT1") (pin "1") (pinfunction "B_1") (pintype "passive"))
    )
    (net (code "109") (name "Net-(VT2-B)") (class "Default")
      (node (ref "R26") (pin "2") (pinfunction "2_2") (pintype "passive"))
      (node (ref "VT2") (pin "1") (pinfunction "B_1") (pintype "passive"))
    )
    (net (code "110") (name "OUT_A1") (class "Default")
      (node (ref "DD1") (pin "11") (pinfunction "OUT_A_11") (pintype "passive"))
      (node (ref "TP10") (pin "1") (pinfunction "G9_1") (pintype "passive"))
      (node (ref "X2") (pin "4") (pinfunction "4_4") (pintype "passive"))
    )
    (net (code "111") (name "OUT_A2") (class "Default")
      (node (ref "DD4") (pin "11") (pinfunction "OUT_A_11") (pintype "passive"))
      (node (ref "TP21") (pin "1") (pinfunction "G9_1") (pintype "passive"))
      (node (ref "X7") (pin "4") (pinfunction "4_4") (pintype "passive"))
    )
    (net (code "112") (name "OUT_B1") (class "Default")
      (node (ref "DD1") (pin "14") (pinfunction "OUT_B_14") (pintype "passive"))
      (node (ref "TP7") (pin "1") (pinfunction "G9_1") (pintype "passive"))
      (node (ref "X2") (pin "1") (pinfunction "1_1") (pintype "passive"))
    )
    (net (code "113") (name "OUT_B2") (class "Default")
      (node (ref "DD4") (pin "14") (pinfunction "OUT_B_14") (pintype "passive"))
      (node (ref "TP18") (pin "1") (pinfunction "G9_1") (pintype "passive"))
      (node (ref "X7") (pin "1") (pinfunction "1_1") (pintype "passive"))
    )
    (net (code "114") (name "PWM_1") (class "Default")
      (node (ref "DD2") (pin "3") (pinfunction "VIN+_3") (pintype "passive"))
      (node (ref "R9") (pin "2") (pinfunction "2_2") (pintype "passive"))
      (node (ref "TP4") (pin "1") (pinfunction "G9_1") (pintype "passive"))
      (node (ref "U7") (pin "15") (pinfunction "PB0/PB1/PB2/PA8_15") (pintype "bidirectional"))
    )
    (net (code "115") (name "PWM_2") (class "Default")
      (node (ref "DD5") (pin "3") (pinfunction "VIN+_3") (pintype "passive"))
      (node (ref "R30") (pin "2") (pinfunction "2_2") (pintype "passive"))
      (node (ref "TP15") (pin "1") (pinfunction "G9_1") (pintype "passive"))
      (node (ref "U7") (pin "13") (pinfunction "PA6_13") (pintype "bidirectional"))
    )
    (net (code "116") (name "PWM_SET_1") (class "Default")
      (node (ref "DA1") (pin "1") (pinfunction "ANODE_1") (pintype "passive"))
      (node (ref "U7") (pin "16") (pinfunction "PA11[PA9]_16") (pintype "bidirectional"))
    )
    (net (code "117") (name "PWM_SET_2") (class "Default")
      (node (ref "DA3") (pin "1") (pinfunction "ANODE_1") (pintype "passive"))
      (node (ref "U7") (pin "14") (pinfunction "PA7_14") (pintype "bidirectional"))
    )
    (net (code "118") (name "SD_1") (class "Default")
      (node (ref "R5") (pin "1") (pinfunction "1_1") (pintype "passive"))
      (node (ref "U7") (pin "11") (pinfunction "PA4_11") (pintype "bidirectional"))
    )
    (net (code "119") (name "SD_2") (class "Default")
      (node (ref "R26") (pin "1") (pinfunction "1_1") (pintype "passive"))
      (node (ref "U7") (pin "12") (pinfunction "PA5_12") (pintype "bidirectional"))
    )
    (net (code "120") (name "SD_G_1") (class "Default")
      (node (ref "DA2") (pin "4") (pinfunction "COLLECTOR_4") (pintype "passive"))
      (node (ref "R15") (pin "2") (pinfunction "2_2") (pintype "passive"))
      (node (ref "TP52") (pin "1") (pinfunction "G9_1") (pintype "passive"))
      (node (ref "X4") (pin "1") (pinfunction "1_1") (pintype "passive"))
    )
    (net (code "121") (name "SD_G_2") (class "Default")
      (node (ref "DA4") (pin "4") (pinfunction "COLLECTOR_4") (pintype "passive"))
      (node (ref "R36") (pin "2") (pinfunction "2_2") (pintype "passive"))
      (node (ref "TP53") (pin "1") (pinfunction "G9_1") (pintype "passive"))
      (node (ref "X8") (pin "1") (pinfunction "1_1") (pintype "passive"))
    )
    (net (code "122") (name "unconnected-(DD1-OSC_OUT-Pad4)") (class "Default")
      (node (ref "DD1") (pin "4") (pinfunction "OSC_OUT_4") (pintype "passive"))
    )
    (net (code "123") (name "unconnected-(DD4-OSC_OUT-Pad4)") (class "Default")
      (node (ref "DD4") (pin "4") (pinfunction "OSC_OUT_4") (pintype "passive"))
    )
    (net (code "124") (name "unconnected-(U6-VIA-Pad3)") (class "Default")
      (node (ref "U6") (pin "3") (pinfunction "VIA_3") (pintype "input"))
    )
    (net (code "125") (name "unconnected-(U6-VOA-Pad14)") (class "Default")
      (node (ref "U6") (pin "14") (pinfunction "VOA_14") (pintype "tri_state"))
    )
  )
)
